# psu_ctrl_brd.net
KiCad netlist of a schematic drawn in EAGLE
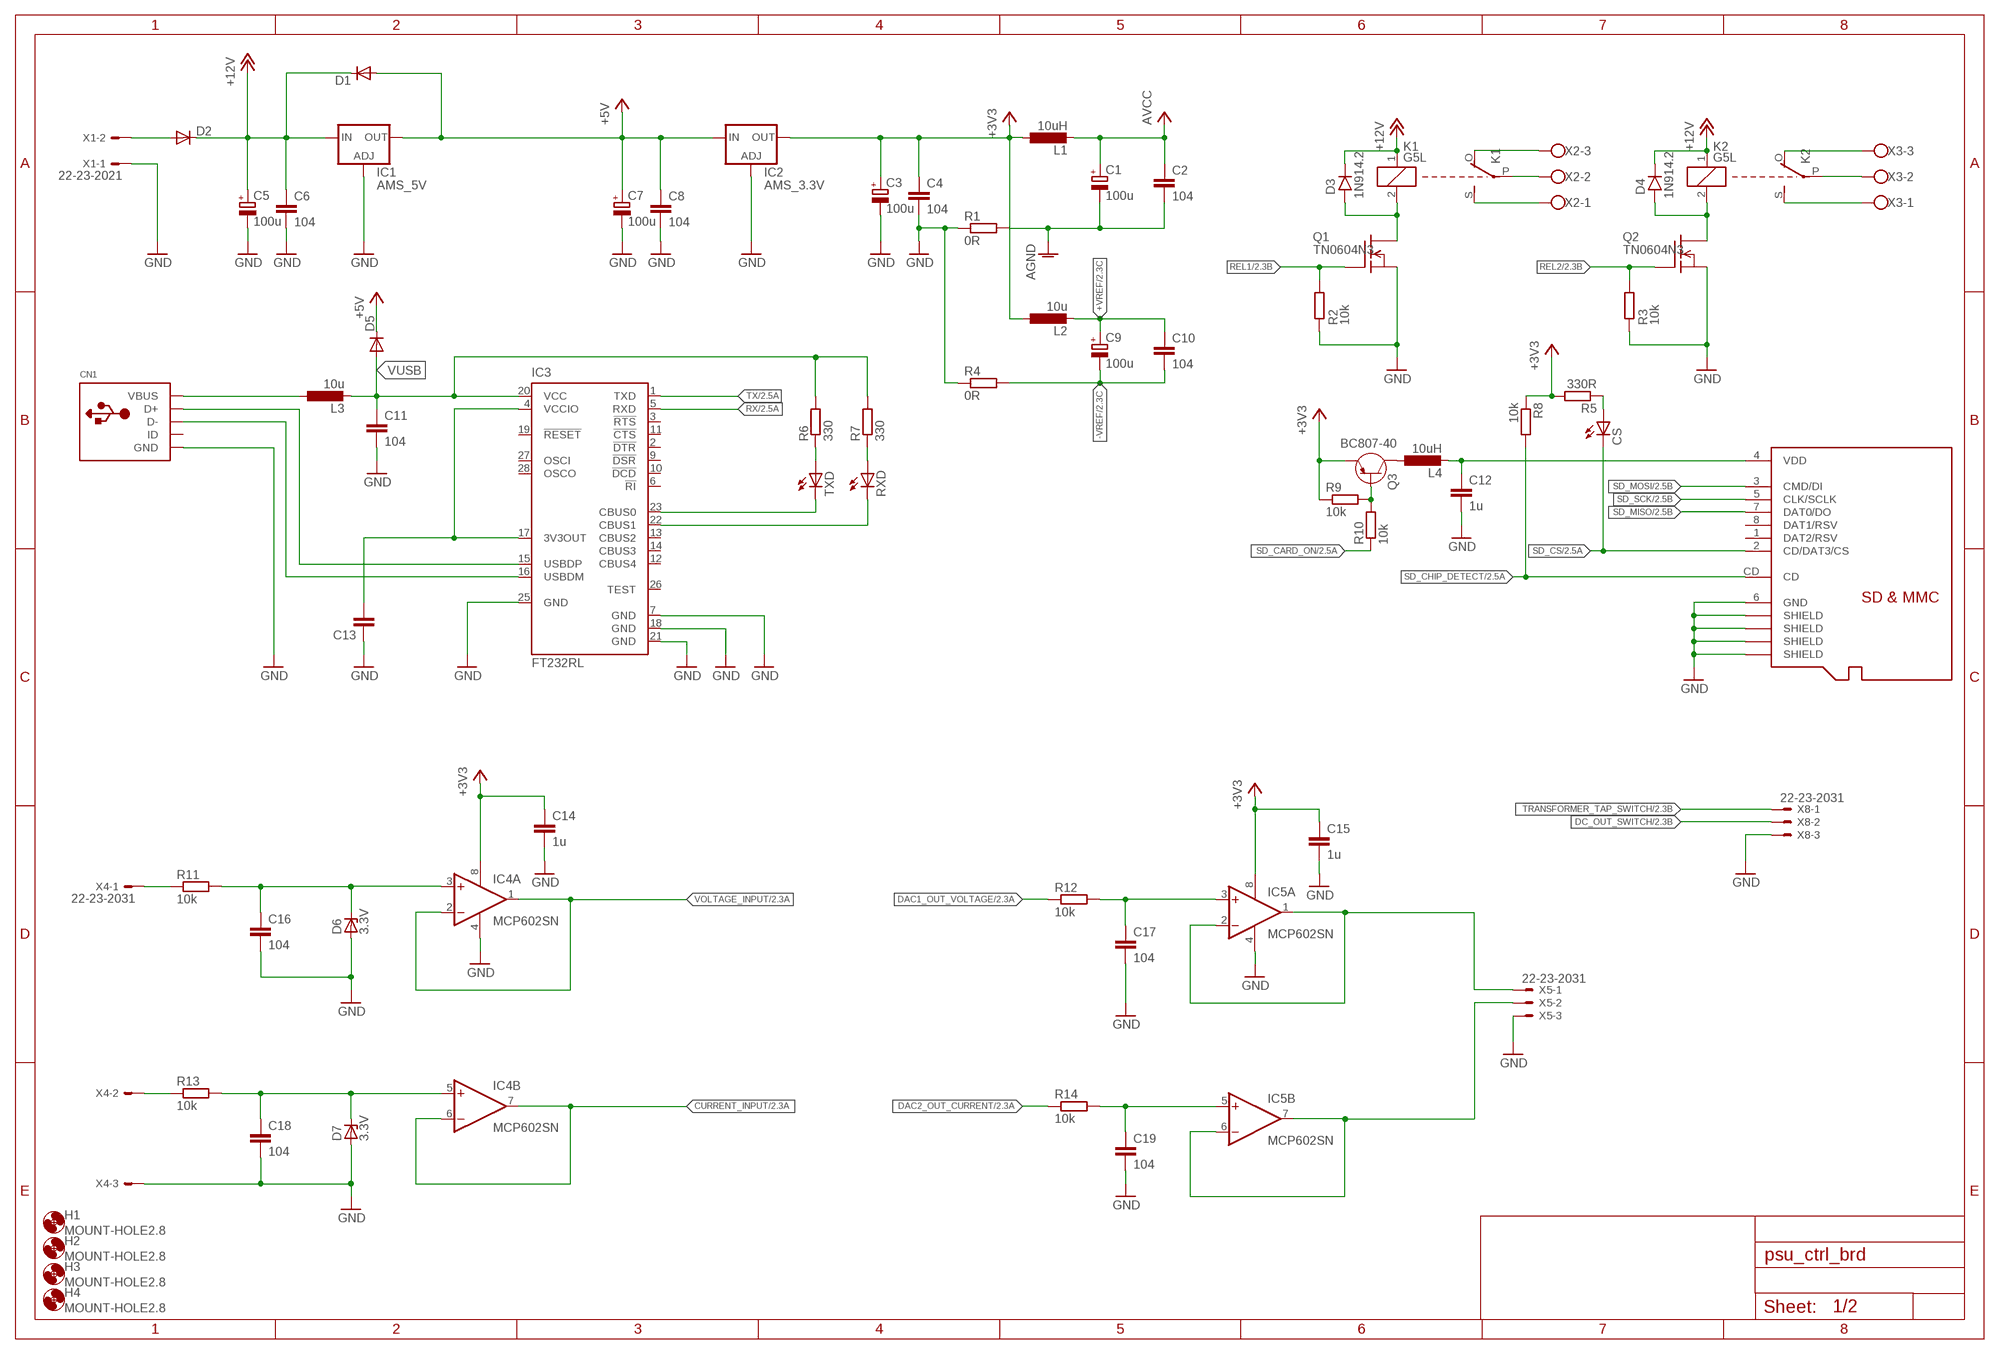
[diagram p0: schematic, sheet 1]
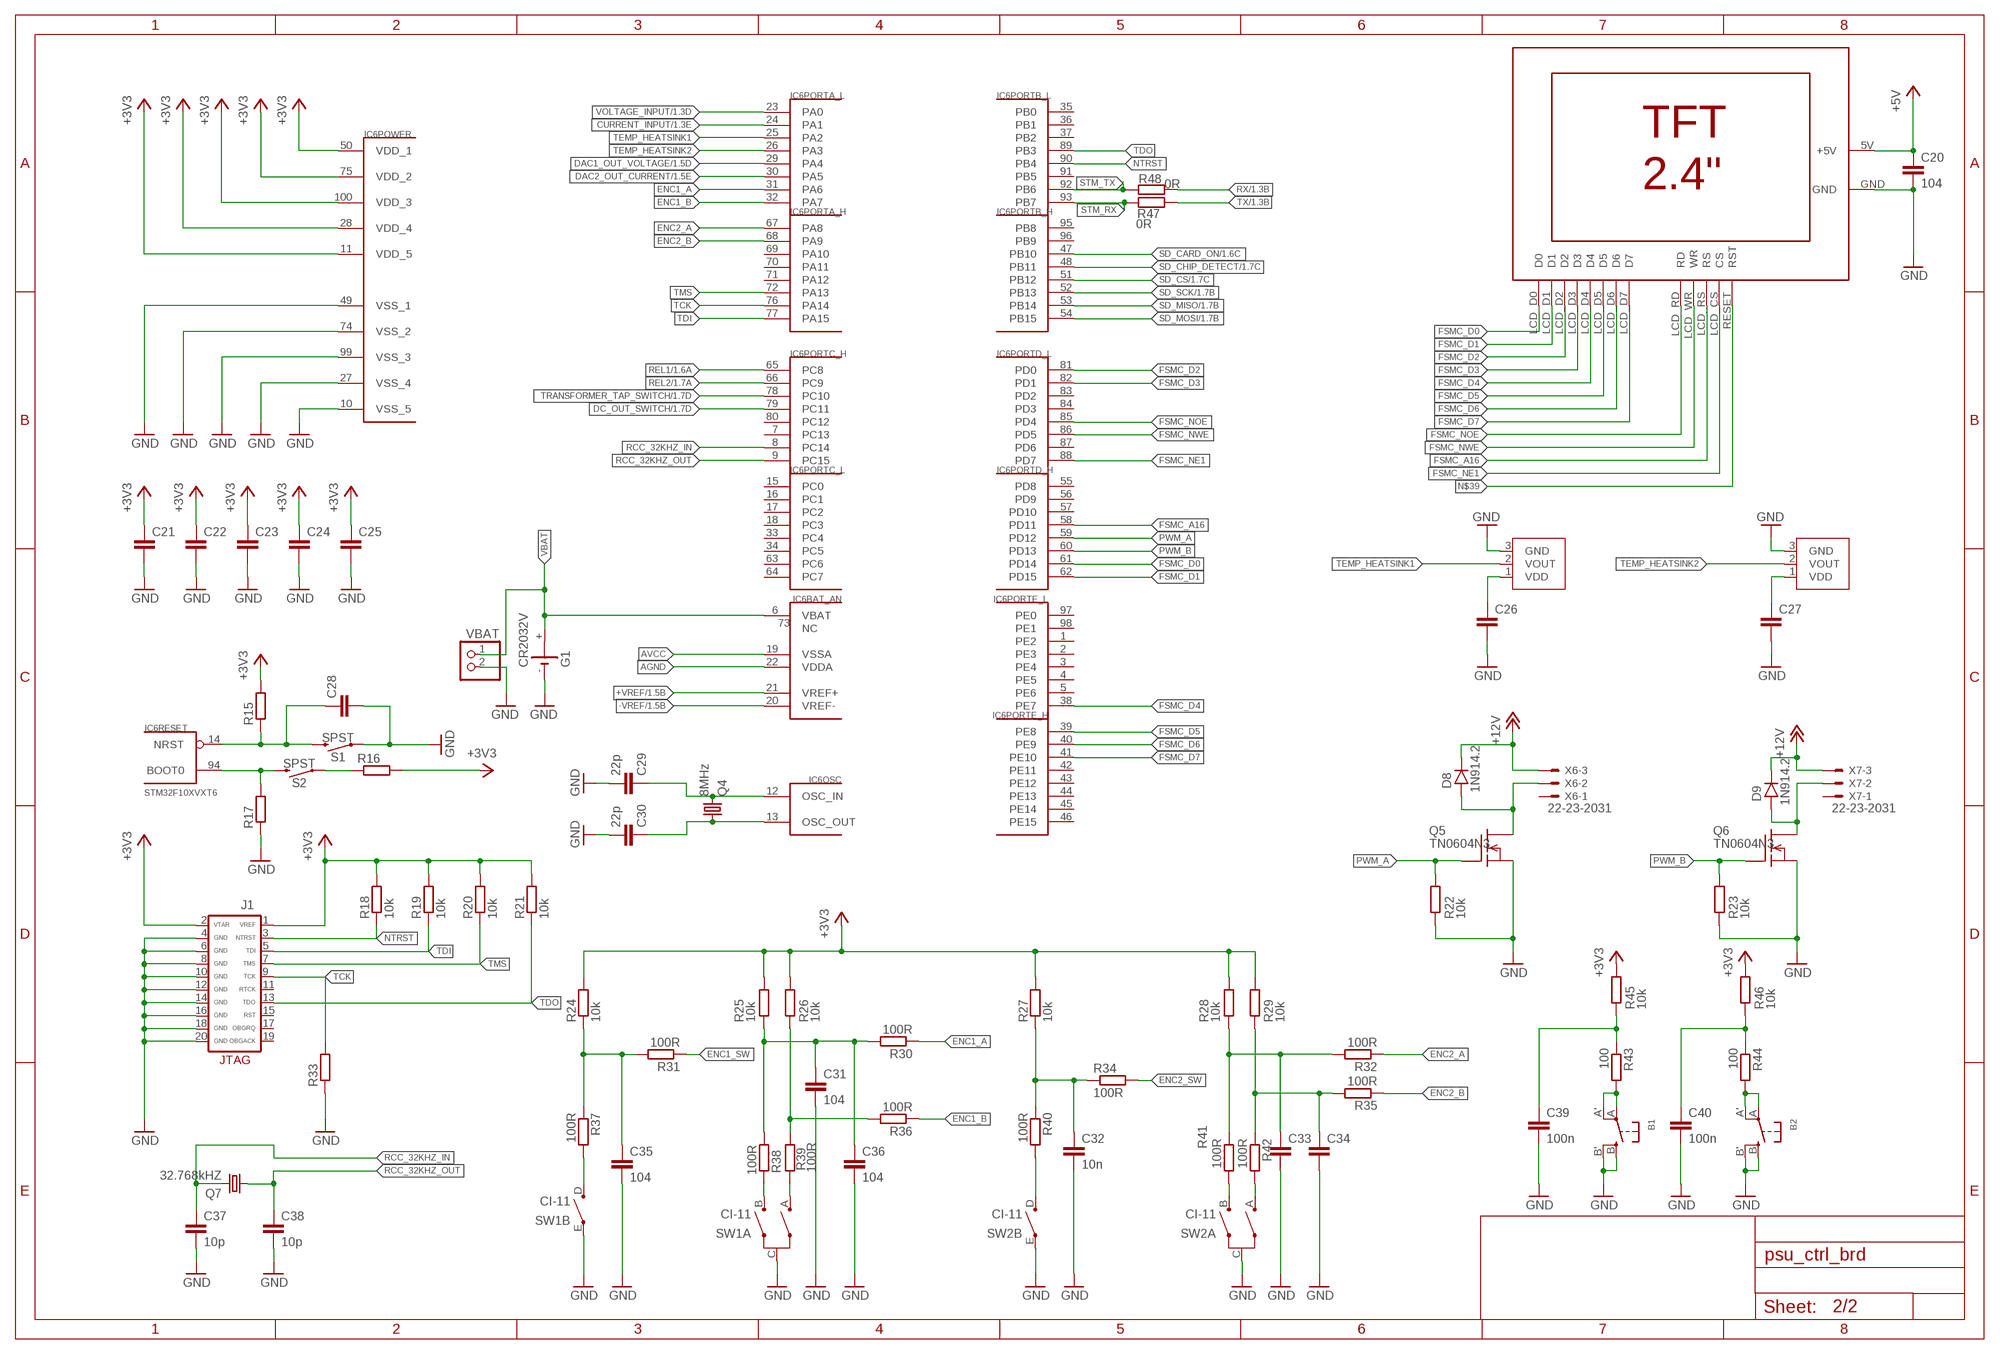
[diagram p1: schematic, sheet 2]

(export (version "E")
  (design (tool "Eeschema 10.0.6"))
  (components
    (comp (ref "B1")
      (value "SWITCH_TACT_SMT")
      (footprint "eagle-import:EVQ-Q2")
      (libsource (lib "eagle-import") (part "SWITCH_TACT_SMT"))
    )
    (comp (ref "B2")
      (value "SWITCH_TACT_SMT")
      (footprint "eagle-import:EVQ-Q2")
      (libsource (lib "eagle-import") (part "SWITCH_TACT_SMT"))
    )
    (comp (ref "C20")
      (value "104")
      (footprint "eagle-import:C0805")
      (libsource (lib "eagle-import") (part "C-EUC0805"))
    )
    (comp (ref "C21")
      (value "C-EUC0805")
      (footprint "eagle-import:C0805")
      (libsource (lib "eagle-import") (part "C-EUC0805"))
    )
    (comp (ref "C22")
      (value "C-EUC0805")
      (footprint "eagle-import:C0805")
      (libsource (lib "eagle-import") (part "C-EUC0805"))
    )
    (comp (ref "C23")
      (value "C-EUC0805")
      (footprint "eagle-import:C0805")
      (libsource (lib "eagle-import") (part "C-EUC0805"))
    )
    (comp (ref "C24")
      (value "C-EUC0805")
      (footprint "eagle-import:C0805")
      (libsource (lib "eagle-import") (part "C-EUC0805"))
    )
    (comp (ref "C25")
      (value "C-EUC0805")
      (footprint "eagle-import:C0805")
      (libsource (lib "eagle-import") (part "C-EUC0805"))
    )
    (comp (ref "C26")
      (value "C-EUC0805")
      (footprint "eagle-import:C0805")
      (libsource (lib "eagle-import") (part "C-EUC0805"))
    )
    (comp (ref "C27")
      (value "C-EUC0805")
      (footprint "eagle-import:C0805")
      (libsource (lib "eagle-import") (part "C-EUC0805"))
    )
    (comp (ref "C28")
      (value "C-EUC0805")
      (footprint "eagle-import:C0805")
      (libsource (lib "eagle-import") (part "C-EUC0805"))
    )
    (comp (ref "C29")
      (value "22p")
      (footprint "eagle-import:C0805")
      (libsource (lib "eagle-import") (part "C-EUC0805"))
    )
    (comp (ref "C30")
      (value "22p")
      (footprint "eagle-import:C0805")
      (libsource (lib "eagle-import") (part "C-EUC0805"))
    )
    (comp (ref "C31")
      (value "104")
      (footprint "eagle-import:C0805")
      (libsource (lib "eagle-import") (part "C-EUC0805"))
    )
    (comp (ref "C32")
      (value "10n")
      (footprint "eagle-import:C0805")
      (libsource (lib "eagle-import") (part "C-EUC0805"))
    )
    (comp (ref "C33")
      (value "C-EUC0805")
      (footprint "eagle-import:C0805")
      (libsource (lib "eagle-import") (part "C-EUC0805"))
    )
    (comp (ref "C34")
      (value "C-EUC0805")
      (footprint "eagle-import:C0805")
      (libsource (lib "eagle-import") (part "C-EUC0805"))
    )
    (comp (ref "C35")
      (value "104")
      (footprint "eagle-import:C0805")
      (libsource (lib "eagle-import") (part "C-EUC0805"))
    )
    (comp (ref "C36")
      (value "104")
      (footprint "eagle-import:C0805")
      (libsource (lib "eagle-import") (part "C-EUC0805"))
    )
    (comp (ref "C37")
      (value "10p")
      (footprint "eagle-import:C0805")
      (libsource (lib "eagle-import") (part "C-EUC0805"))
    )
    (comp (ref "C38")
      (value "10p")
      (footprint "eagle-import:C0805")
      (libsource (lib "eagle-import") (part "C-EUC0805"))
    )
    (comp (ref "C39")
      (value "100n")
      (footprint "eagle-import:C0805")
      (libsource (lib "eagle-import") (part "C-EUC0805"))
    )
    (comp (ref "C40")
      (value "100n")
      (footprint "eagle-import:C0805")
      (libsource (lib "eagle-import") (part "C-EUC0805"))
    )
    (comp (ref "D8")
      (value "1N914.2")
      (footprint "eagle-import:DO35-2")
      (libsource (lib "eagle-import") (part "1N914.2"))
    )
    (comp (ref "D9")
      (value "1N914.2")
      (footprint "eagle-import:DO35-2")
      (libsource (lib "eagle-import") (part "1N914.2"))
    )
    (comp (ref "G1")
      (value "CR2032V")
      (footprint "eagle-import:CR2032V")
      (libsource (lib "eagle-import") (part "CR2032V"))
    )
    (comp (ref "IC6")
      (value "STM32F10XVXT6")
      (footprint "eagle-import:TQFP100")
      (libsource (lib "eagle-import") (part "STM32F10XVXT6"))
    )
    (comp (ref "J1")
      (value "JTAG-ARM-PAK100/2500-20")
      (footprint "eagle-import:PAK100_2500-20")
      (libsource (lib "eagle-import") (part "JTAG-ARM-PAK100/2500-20"))
    )
    (comp (ref "MCP97X_1")
      (value "MCP970XTO")
      (footprint "eagle-import:TO92")
      (libsource (lib "eagle-import") (part "MCP970XTO"))
    )
    (comp (ref "MCP97X_2")
      (value "MCP970XTO")
      (footprint "eagle-import:TO92")
      (libsource (lib "eagle-import") (part "MCP970XTO"))
    )
    (comp (ref "Q4")
      (value "8MHz")
      (footprint "eagle-import:CSM-7X-DU")
      (libsource (lib "eagle-import") (part "CSM-7X-DU"))
    )
    (comp (ref "Q5")
      (value "TN0604N3")
      (footprint "eagle-import:TO-92")
      (libsource (lib "eagle-import") (part "TN0604N3"))
    )
    (comp (ref "Q6")
      (value "TN0604N3")
      (footprint "eagle-import:TO-92")
      (libsource (lib "eagle-import") (part "TN0604N3"))
    )
    (comp (ref "Q7")
      (value "32.768kHZ")
      (footprint "eagle-import:TC26V")
      (libsource (lib "eagle-import") (part "CRYSTALTC26V"))
    )
    (comp (ref "R15")
      (value "R-EU_R0805")
      (footprint "eagle-import:R0805")
      (libsource (lib "eagle-import") (part "R-EU_R0805"))
    )
    (comp (ref "R16")
      (value "R-EU_R0805")
      (footprint "eagle-import:R0805")
      (libsource (lib "eagle-import") (part "R-EU_R0805"))
    )
    (comp (ref "R17")
      (value "R-EU_R0805")
      (footprint "eagle-import:R0805")
      (libsource (lib "eagle-import") (part "R-EU_R0805"))
    )
    (comp (ref "R18")
      (value "10k")
      (footprint "eagle-import:R0805")
      (libsource (lib "eagle-import") (part "R-EU_R0805"))
    )
    (comp (ref "R19")
      (value "10k")
      (footprint "eagle-import:R0805")
      (libsource (lib "eagle-import") (part "R-EU_R0805"))
    )
    (comp (ref "R20")
      (value "10k")
      (footprint "eagle-import:R0805")
      (libsource (lib "eagle-import") (part "R-EU_R0805"))
    )
    (comp (ref "R21")
      (value "10k")
      (footprint "eagle-import:R0805")
      (libsource (lib "eagle-import") (part "R-EU_R0805"))
    )
    (comp (ref "R22")
      (value "10k")
      (footprint "eagle-import:R0805")
      (libsource (lib "eagle-import") (part "R-EU_R0805"))
    )
    (comp (ref "R23")
      (value "10k")
      (footprint "eagle-import:R0805")
      (libsource (lib "eagle-import") (part "R-EU_R0805"))
    )
    (comp (ref "R24")
      (value "10k")
      (footprint "eagle-import:R0805")
      (libsource (lib "eagle-import") (part "R-EU_R0805"))
    )
    (comp (ref "R25")
      (value "10k")
      (footprint "eagle-import:R0805")
      (libsource (lib "eagle-import") (part "R-EU_R0805"))
    )
    (comp (ref "R26")
      (value "10k")
      (footprint "eagle-import:R0805")
      (libsource (lib "eagle-import") (part "R-EU_R0805"))
    )
    (comp (ref "R27")
      (value "10k")
      (footprint "eagle-import:R0805")
      (libsource (lib "eagle-import") (part "R-EU_R0805"))
    )
    (comp (ref "R28")
      (value "10k")
      (footprint "eagle-import:R0805")
      (libsource (lib "eagle-import") (part "R-EU_R0805"))
    )
    (comp (ref "R29")
      (value "10k")
      (footprint "eagle-import:R0805")
      (libsource (lib "eagle-import") (part "R-EU_R0805"))
    )
    (comp (ref "R30")
      (value "100R")
      (footprint "eagle-import:R0805")
      (libsource (lib "eagle-import") (part "R-EU_R0805"))
    )
    (comp (ref "R31")
      (value "100R")
      (footprint "eagle-import:R0805")
      (libsource (lib "eagle-import") (part "R-EU_R0805"))
    )
    (comp (ref "R32")
      (value "100R")
      (footprint "eagle-import:R0805")
      (libsource (lib "eagle-import") (part "R-EU_R0805"))
    )
    (comp (ref "R33")
      (value "R-EU_R0805")
      (footprint "eagle-import:R0805")
      (libsource (lib "eagle-import") (part "R-EU_R0805"))
    )
    (comp (ref "R34")
      (value "100R")
      (footprint "eagle-import:R0805")
      (libsource (lib "eagle-import") (part "R-EU_R0805"))
    )
    (comp (ref "R35")
      (value "100R")
      (footprint "eagle-import:R0805")
      (libsource (lib "eagle-import") (part "R-EU_R0805"))
    )
    (comp (ref "R36")
      (value "100R")
      (footprint "eagle-import:R0805")
      (libsource (lib "eagle-import") (part "R-EU_R0805"))
    )
    (comp (ref "R37")
      (value "100R")
      (footprint "eagle-import:R0805")
      (libsource (lib "eagle-import") (part "R-EU_R0805"))
    )
    (comp (ref "R38")
      (value "100R")
      (footprint "eagle-import:R0805")
      (libsource (lib "eagle-import") (part "R-EU_R0805"))
    )
    (comp (ref "R39")
      (value "100R")
      (footprint "eagle-import:R0805")
      (libsource (lib "eagle-import") (part "R-EU_R0805"))
    )
    (comp (ref "R40")
      (value "100R")
      (footprint "eagle-import:R0805")
      (libsource (lib "eagle-import") (part "R-EU_R0805"))
    )
    (comp (ref "R41")
      (value "100R")
      (footprint "eagle-import:R0805")
      (libsource (lib "eagle-import") (part "R-EU_R0805"))
    )
    (comp (ref "R42")
      (value "100R")
      (footprint "eagle-import:R0805")
      (libsource (lib "eagle-import") (part "R-EU_R0805"))
    )
    (comp (ref "R43")
      (value "100")
      (footprint "eagle-import:R0805")
      (libsource (lib "eagle-import") (part "R-EU_R0805"))
    )
    (comp (ref "R44")
      (value "100")
      (footprint "eagle-import:R0805")
      (libsource (lib "eagle-import") (part "R-EU_R0805"))
    )
    (comp (ref "R45")
      (value "10k")
      (footprint "eagle-import:R0805")
      (libsource (lib "eagle-import") (part "R-EU_R0805"))
    )
    (comp (ref "R46")
      (value "10k")
      (footprint "eagle-import:R0805")
      (libsource (lib "eagle-import") (part "R-EU_R0805"))
    )
    (comp (ref "R47")
      (value "0R")
      (footprint "eagle-import:R0805")
      (libsource (lib "eagle-import") (part "R-EU_R0805"))
    )
    (comp (ref "R48")
      (value "0R")
      (footprint "eagle-import:R0805")
      (libsource (lib "eagle-import") (part "R-EU_R0805"))
    )
    (comp (ref "S1")
      (value "SPST")
      (footprint "eagle-import:TACTILE_SWITCH_SMD_6.0X3.5MM")
      (libsource (lib "eagle-import") (part "MOMENTARY-SWITCH-SPST-SMD-6.0X3.5MM"))
    )
    (comp (ref "S2")
      (value "SPST")
      (footprint "eagle-import:TACTILE_SWITCH_SMD_6.0X3.5MM")
      (libsource (lib "eagle-import") (part "MOMENTARY-SWITCH-SPST-SMD-6.0X3.5MM"))
    )
    (comp (ref "SW1")
      (value "CI-11")
      (footprint "eagle-import:CI-11")
      (libsource (lib "eagle-import") (part "CI-11"))
    )
    (comp (ref "SW2")
      (value "CI-11")
      (footprint "eagle-import:CI-11")
      (libsource (lib "eagle-import") (part "CI-11"))
    )
    (comp (ref "U$2")
      (value "TFT24")
      (footprint "eagle-import:A")
      (libsource (lib "eagle-import") (part "TFT24"))
    )
    (comp (ref "VBAT")
      (value "PINHD-1X2")
      (footprint "eagle-import:1X02")
      (libsource (lib "eagle-import") (part "PINHD-1X2"))
    )
    (comp (ref "X6")
      (value "22-23-2031")
      (footprint "eagle-import:22-23-2031")
      (fields (field (name "MF") "MOLEX"))
      (libsource (lib "eagle-import") (part "22-23-2031"))
    )
    (comp (ref "X7")
      (value "22-23-2031")
      (footprint "eagle-import:22-23-2031")
      (fields (field (name "MF") "MOLEX"))
      (libsource (lib "eagle-import") (part "22-23-2031"))
    )
    (comp (ref "C1")
      (value "100u")
      (footprint "eagle-import:153CLV-0505")
      (libsource (lib "eagle-import") (part "CPOL-EU153CLV-0505"))
    )
    (comp (ref "C2")
      (value "104")
      (footprint "eagle-import:C0805")
      (libsource (lib "eagle-import") (part "C-EUC0805"))
    )
    (comp (ref "C3")
      (value "100u")
      (footprint "eagle-import:153CLV-0505")
      (libsource (lib "eagle-import") (part "CPOL-EU153CLV-0505"))
    )
    (comp (ref "C4")
      (value "104")
      (footprint "eagle-import:C0805")
      (libsource (lib "eagle-import") (part "C-EUC0805"))
    )
    (comp (ref "C5")
      (value "100u")
      (footprint "eagle-import:153CLV-0505")
      (libsource (lib "eagle-import") (part "CPOL-EU153CLV-0505"))
    )
    (comp (ref "C6")
      (value "104")
      (footprint "eagle-import:C0805")
      (libsource (lib "eagle-import") (part "C-EUC0805"))
    )
    (comp (ref "C7")
      (value "100u")
      (footprint "eagle-import:153CLV-0505")
      (libsource (lib "eagle-import") (part "CPOL-EU153CLV-0505"))
    )
    (comp (ref "C8")
      (value "104")
      (footprint "eagle-import:C0805")
      (libsource (lib "eagle-import") (part "C-EUC0805"))
    )
    (comp (ref "C9")
      (value "100u")
      (footprint "eagle-import:153CLV-0505")
      (libsource (lib "eagle-import") (part "CPOL-EU153CLV-0505"))
    )
    (comp (ref "C10")
      (value "104")
      (footprint "eagle-import:C0805")
      (libsource (lib "eagle-import") (part "C-EUC0805"))
    )
    (comp (ref "C11")
      (value "104")
      (footprint "eagle-import:C0805")
      (libsource (lib "eagle-import") (part "C-EUC0805"))
    )
    (comp (ref "C12")
      (value "1u")
      (footprint "eagle-import:C0805")
      (libsource (lib "eagle-import") (part "C-EUC0805"))
    )
    (comp (ref "C13")
      (value "C-EUC0805")
      (footprint "eagle-import:C0805")
      (libsource (lib "eagle-import") (part "C-EUC0805"))
    )
    (comp (ref "C14")
      (value "1u")
      (footprint "eagle-import:C0805")
      (libsource (lib "eagle-import") (part "C-EUC0805"))
    )
    (comp (ref "C15")
      (value "1u")
      (footprint "eagle-import:C0805")
      (libsource (lib "eagle-import") (part "C-EUC0805"))
    )
    (comp (ref "C16")
      (value "104")
      (footprint "eagle-import:C0805")
      (libsource (lib "eagle-import") (part "C-EUC0805"))
    )
    (comp (ref "C17")
      (value "104")
      (footprint "eagle-import:C0805")
      (libsource (lib "eagle-import") (part "C-EUC0805"))
    )
    (comp (ref "C18")
      (value "104")
      (footprint "eagle-import:C0805")
      (libsource (lib "eagle-import") (part "C-EUC0805"))
    )
    (comp (ref "C19")
      (value "104")
      (footprint "eagle-import:C0805")
      (libsource (lib "eagle-import") (part "C-EUC0805"))
    )
    (comp (ref "CN1")
      (value "USBMINIB")
      (footprint "eagle-import:USB-MINIB")
      (libsource (lib "eagle-import") (part "USBMINIB"))
    )
    (comp (ref "CS")
      (value "LEDCHIPLED_1206")
      (footprint "eagle-import:CHIPLED_1206")
      (libsource (lib "eagle-import") (part "LEDCHIPLED_1206"))
    )
    (comp (ref "D1")
      (value "DIODE-DO-214AC")
      (footprint "eagle-import:DO-214AC")
      (libsource (lib "eagle-import") (part "DIODE-DO-214AC"))
    )
    (comp (ref "D2")
      (value "DIODE-DO-214AC")
      (footprint "eagle-import:DO-214AC")
      (libsource (lib "eagle-import") (part "DIODE-DO-214AC"))
    )
    (comp (ref "D3")
      (value "1N914.2")
      (footprint "eagle-import:DO35-2")
      (libsource (lib "eagle-import") (part "1N914.2"))
    )
    (comp (ref "D4")
      (value "1N914.2")
      (footprint "eagle-import:DO35-2")
      (libsource (lib "eagle-import") (part "1N914.2"))
    )
    (comp (ref "D5")
      (value "DIODE-DO-214AC")
      (footprint "eagle-import:DO-214AC")
      (libsource (lib "eagle-import") (part "DIODE-DO-214AC"))
    )
    (comp (ref "D6")
      (value "3.3V")
      (footprint "eagle-import:SOD81")
      (libsource (lib "eagle-import") (part "BZD23"))
    )
    (comp (ref "D7")
      (value "3.3V")
      (footprint "eagle-import:SOD81")
      (libsource (lib "eagle-import") (part "BZD23"))
    )
    (comp (ref "H1")
      (value "MOUNT-HOLE2.8")
      (footprint "eagle-import:2,8")
      (libsource (lib "eagle-import") (part "MOUNT-HOLE2.8"))
    )
    (comp (ref "H2")
      (value "MOUNT-HOLE2.8")
      (footprint "eagle-import:2,8")
      (libsource (lib "eagle-import") (part "MOUNT-HOLE2.8"))
    )
    (comp (ref "H3")
      (value "MOUNT-HOLE2.8")
      (footprint "eagle-import:2,8")
      (libsource (lib "eagle-import") (part "MOUNT-HOLE2.8"))
    )
    (comp (ref "H4")
      (value "MOUNT-HOLE2.8")
      (footprint "eagle-import:2,8")
      (libsource (lib "eagle-import") (part "MOUNT-HOLE2.8"))
    )
    (comp (ref "IC1")
      (value "AMS_5V")
      (footprint "eagle-import:SOT223")
      (libsource (lib "eagle-import") (part "LD117A?S50TR"))
    )
    (comp (ref "IC2")
      (value "AMS_3.3V")
      (footprint "eagle-import:SOT223")
      (libsource (lib "eagle-import") (part "LD117A?S50TR"))
    )
    (comp (ref "IC3")
      (value "FT232RL")
      (footprint "eagle-import:SSOP28")
      (libsource (lib "eagle-import") (part "FT232RL"))
    )
    (comp (ref "IC4")
      (value "MCP602SN")
      (footprint "eagle-import:SO08")
      (libsource (lib "eagle-import") (part "MCP602SN"))
    )
    (comp (ref "IC5")
      (value "MCP602SN")
      (footprint "eagle-import:SO08")
      (libsource (lib "eagle-import") (part "MCP602SN"))
    )
    (comp (ref "K1")
      (value "G5L")
      (footprint "eagle-import:G5LE")
      (libsource (lib "eagle-import") (part "G5L"))
    )
    (comp (ref "K2")
      (value "G5L")
      (footprint "eagle-import:G5LE")
      (libsource (lib "eagle-import") (part "G5L"))
    )
    (comp (ref "L1")
      (value "10uH")
      (footprint "eagle-import:0207_2V")
      (libsource (lib "eagle-import") (part "L-EU0207/2V"))
    )
    (comp (ref "L2")
      (value "10u")
      (footprint "eagle-import:0207_2V")
      (libsource (lib "eagle-import") (part "L-EU0207/2V"))
    )
    (comp (ref "L3")
      (value "10u")
      (footprint "eagle-import:0207_2V")
      (libsource (lib "eagle-import") (part "L-EU0207/2V"))
    )
    (comp (ref "L4")
      (value "10uH")
      (footprint "eagle-import:0207_2V")
      (libsource (lib "eagle-import") (part "L-EU0207/2V"))
    )
    (comp (ref "Q1")
      (value "TN0604N3")
      (footprint "eagle-import:TO-92")
      (libsource (lib "eagle-import") (part "TN0604N3"))
    )
    (comp (ref "Q2")
      (value "TN0604N3")
      (footprint "eagle-import:TO-92")
      (libsource (lib "eagle-import") (part "TN0604N3"))
    )
    (comp (ref "Q3")
      (value "BC807-40")
      (footprint "eagle-import:SOT23")
      (libsource (lib "eagle-import") (part "BC807-40"))
    )
    (comp (ref "R1")
      (value "0R")
      (footprint "eagle-import:M0805")
      (libsource (lib "eagle-import") (part "R-EU_M0805"))
    )
    (comp (ref "R2")
      (value "10k")
      (footprint "eagle-import:R0805")
      (libsource (lib "eagle-import") (part "R-EU_R0805"))
    )
    (comp (ref "R3")
      (value "10k")
      (footprint "eagle-import:R0805")
      (libsource (lib "eagle-import") (part "R-EU_R0805"))
    )
    (comp (ref "R4")
      (value "0R")
      (footprint "eagle-import:M0805")
      (libsource (lib "eagle-import") (part "R-EU_M0805"))
    )
    (comp (ref "R5")
      (value "330R")
      (footprint "eagle-import:M0805")
      (libsource (lib "eagle-import") (part "R-EU_M0805"))
    )
    (comp (ref "R6")
      (value "330")
      (footprint "eagle-import:M0805")
      (libsource (lib "eagle-import") (part "R-EU_M0805"))
    )
    (comp (ref "R7")
      (value "330")
      (footprint "eagle-import:M0805")
      (libsource (lib "eagle-import") (part "R-EU_M0805"))
    )
    (comp (ref "R8")
      (value "10k")
      (footprint "eagle-import:M0805")
      (libsource (lib "eagle-import") (part "R-EU_M0805"))
    )
    (comp (ref "R9")
      (value "10k")
      (footprint "eagle-import:M0805")
      (libsource (lib "eagle-import") (part "R-EU_M0805"))
    )
    (comp (ref "R10")
      (value "10k")
      (footprint "eagle-import:M0805")
      (libsource (lib "eagle-import") (part "R-EU_M0805"))
    )
    (comp (ref "R11")
      (value "10k")
      (footprint "eagle-import:M0805")
      (libsource (lib "eagle-import") (part "R-EU_M0805"))
    )
    (comp (ref "R12")
      (value "10k")
      (footprint "eagle-import:M0805")
      (libsource (lib "eagle-import") (part "R-EU_M0805"))
    )
    (comp (ref "R13")
      (value "10k")
      (footprint "eagle-import:M0805")
      (libsource (lib "eagle-import") (part "R-EU_M0805"))
    )
    (comp (ref "R14")
      (value "10k")
      (footprint "eagle-import:M0805")
      (libsource (lib "eagle-import") (part "R-EU_M0805"))
    )
    (comp (ref "RXD")
      (value "LEDCHIPLED_1206")
      (footprint "eagle-import:CHIPLED_1206")
      (libsource (lib "eagle-import") (part "LEDCHIPLED_1206"))
    )
    (comp (ref "TXD")
      (value "LEDCHIPLED_1206")
      (footprint "eagle-import:CHIPLED_1206")
      (libsource (lib "eagle-import") (part "LEDCHIPLED_1206"))
    )
    (comp (ref "U$1")
      (value "MICROSD")
      (footprint "eagle-import:C12075")
      (libsource (lib "eagle-import") (part "MICROSD"))
    )
    (comp (ref "X1")
      (value "22-23-2021")
      (footprint "eagle-import:22-23-2021")
      (fields (field (name "MF") "MOLEX"))
      (libsource (lib "eagle-import") (part "22-23-2021"))
    )
    (comp (ref "X2")
      (value "AK500/3")
      (footprint "eagle-import:AK500_3")
      (libsource (lib "eagle-import") (part "AK500/3"))
    )
    (comp (ref "X3")
      (value "AK500/3")
      (footprint "eagle-import:AK500_3")
      (libsource (lib "eagle-import") (part "AK500/3"))
    )
    (comp (ref "X4")
      (value "22-23-2031")
      (footprint "eagle-import:22-23-2031")
      (fields (field (name "MF") "MOLEX"))
      (libsource (lib "eagle-import") (part "22-23-2031"))
    )
    (comp (ref "X5")
      (value "22-23-2031")
      (footprint "eagle-import:22-23-2031")
      (fields (field (name "MF") "MOLEX"))
      (libsource (lib "eagle-import") (part "22-23-2031"))
    )
    (comp (ref "X8")
      (value "22-23-2031")
      (footprint "eagle-import:22-23-2031")
      (fields (field (name "MF") "MOLEX"))
      (libsource (lib "eagle-import") (part "22-23-2031"))
    )
  )
  (nets
    (net (code "1") (name "+3V3") (class "Default")
      (node (ref "C14") (pin "1") (pinfunction "1_1") (pintype "passive"))
      (node (ref "C15") (pin "1") (pinfunction "1_1") (pintype "passive"))
      (node (ref "C21") (pin "1") (pinfunction "1_1") (pintype "passive"))
      (node (ref "C22") (pin "1") (pinfunction "1_1") (pintype "passive"))
      (node (ref "C23") (pin "1") (pinfunction "1_1") (pintype "passive"))
      (node (ref "C24") (pin "1") (pinfunction "1_1") (pintype "passive"))
      (node (ref "C25") (pin "1") (pinfunction "1_1") (pintype "passive"))
      (node (ref "C3") (pin "+") (pinfunction "+_+") (pintype "passive"))
      (node (ref "C4") (pin "1") (pinfunction "1_1") (pintype "passive"))
      (node (ref "IC2") (pin "4") (pinfunction "OUT_4") (pintype "passive"))
      (node (ref "IC4") (pin "8") (pinfunction "V+_8") (pintype "power_in"))
      (node (ref "IC5") (pin "8") (pinfunction "V+_8") (pintype "power_in"))
      (node (ref "IC6") (pin "100") (pinfunction "VDD_3_100") (pintype "power_in"))
      (node (ref "IC6") (pin "11") (pinfunction "VDD_5_11") (pintype "power_in"))
      (node (ref "IC6") (pin "28") (pinfunction "VDD_4_28") (pintype "power_in"))
      (node (ref "IC6") (pin "50") (pinfunction "VDD_1_50") (pintype "power_in"))
      (node (ref "IC6") (pin "75") (pinfunction "VDD_2_75") (pintype "power_in"))
      (node (ref "J1") (pin "1") (pinfunction "VREF_1") (pintype "passive"))
      (node (ref "J1") (pin "2") (pinfunction "VTAR_2") (pintype "passive"))
      (node (ref "L1") (pin "1") (pinfunction "1_1") (pintype "passive"))
      (node (ref "L2") (pin "1") (pinfunction "1_1") (pintype "passive"))
      (node (ref "Q3") (pin "2") (pinfunction "E_2") (pintype "passive"))
      (node (ref "R15") (pin "2") (pinfunction "2_2") (pintype "passive"))
      (node (ref "R16") (pin "2") (pinfunction "2_2") (pintype "passive"))
      (node (ref "R18") (pin "2") (pinfunction "2_2") (pintype "passive"))
      (node (ref "R19") (pin "2") (pinfunction "2_2") (pintype "passive"))
      (node (ref "R20") (pin "2") (pinfunction "2_2") (pintype "passive"))
      (node (ref "R21") (pin "2") (pinfunction "2_2") (pintype "passive"))
      (node (ref "R24") (pin "2") (pinfunction "2_2") (pintype "passive"))
      (node (ref "R25") (pin "2") (pinfunction "2_2") (pintype "passive"))
      (node (ref "R26") (pin "2") (pinfunction "2_2") (pintype "passive"))
      (node (ref "R27") (pin "2") (pinfunction "2_2") (pintype "passive"))
      (node (ref "R28") (pin "2") (pinfunction "2_2") (pintype "passive"))
      (node (ref "R29") (pin "2") (pinfunction "2_2") (pintype "passive"))
      (node (ref "R45") (pin "2") (pinfunction "2_2") (pintype "passive"))
      (node (ref "R46") (pin "2") (pinfunction "2_2") (pintype "passive"))
      (node (ref "R5") (pin "2") (pinfunction "2_2") (pintype "passive"))
      (node (ref "R8") (pin "1") (pinfunction "1_1") (pintype "passive"))
      (node (ref "R9") (pin "1") (pinfunction "1_1") (pintype "passive"))
    )
    (net (code "2") (name "+5V") (class "Default")
      (node (ref "C20") (pin "1") (pinfunction "1_1") (pintype "passive"))
      (node (ref "C7") (pin "+") (pinfunction "+_+") (pintype "passive"))
      (node (ref "C8") (pin "1") (pinfunction "1_1") (pintype "passive"))
      (node (ref "D1") (pin "A") (pinfunction "A_A") (pintype "passive"))
      (node (ref "D5") (pin "C") (pinfunction "C_C") (pintype "passive"))
      (node (ref "IC1") (pin "4") (pinfunction "OUT_4") (pintype "passive"))
      (node (ref "IC2") (pin "3") (pinfunction "IN_3") (pintype "input"))
      (node (ref "U$2") (pin "5V") (pinfunction "+5V_5V") (pintype "bidirectional"))
    )
    (net (code "3") (name "+12V") (class "Default")
      (node (ref "C5") (pin "+") (pinfunction "+_+") (pintype "passive"))
      (node (ref "C6") (pin "1") (pinfunction "1_1") (pintype "passive"))
      (node (ref "D1") (pin "C") (pinfunction "C_C") (pintype "passive"))
      (node (ref "D2") (pin "C") (pinfunction "C_C") (pintype "passive"))
      (node (ref "D3") (pin "C") (pinfunction "C_C") (pintype "passive"))
      (node (ref "D4") (pin "C") (pinfunction "C_C") (pintype "passive"))
      (node (ref "D8") (pin "C") (pinfunction "C_C") (pintype "passive"))
      (node (ref "D9") (pin "C") (pinfunction "C_C") (pintype "passive"))
      (node (ref "IC1") (pin "3") (pinfunction "IN_3") (pintype "input"))
      (node (ref "K1") (pin "1") (pinfunction "1_1") (pintype "passive"))
      (node (ref "K2") (pin "1") (pinfunction "1_1") (pintype "passive"))
      (node (ref "X6") (pin "3") (pinfunction "S_3") (pintype "passive"))
      (node (ref "X7") (pin "3") (pinfunction "S_3") (pintype "passive"))
    )
    (net (code "4") (name "+VREF") (class "Default")
      (node (ref "C10") (pin "1") (pinfunction "1_1") (pintype "passive"))
      (node (ref "C9") (pin "+") (pinfunction "+_+") (pintype "passive"))
      (node (ref "IC6") (pin "21") (pinfunction "VREF+_21") (pintype "input"))
      (node (ref "L2") (pin "2") (pinfunction "2_2") (pintype "passive"))
    )
    (net (code "5") (name "-VREF") (class "Default")
      (node (ref "C10") (pin "2") (pinfunction "2_2") (pintype "passive"))
      (node (ref "C9") (pin "-") (pinfunction "-_-") (pintype "passive"))
      (node (ref "IC6") (pin "20") (pinfunction "VREF-_20") (pintype "input"))
      (node (ref "R4") (pin "2") (pinfunction "2_2") (pintype "passive"))
    )
    (net (code "6") (name "AGND") (class "Default")
      (node (ref "C1") (pin "-") (pinfunction "-_-") (pintype "passive"))
      (node (ref "C2") (pin "2") (pinfunction "2_2") (pintype "passive"))
      (node (ref "IC6") (pin "22") (pinfunction "VDDA_22") (pintype "power_in"))
      (node (ref "R1") (pin "2") (pinfunction "2_2") (pintype "passive"))
    )
    (net (code "7") (name "AVCC") (class "Default")
      (node (ref "C1") (pin "+") (pinfunction "+_+") (pintype "passive"))
      (node (ref "C2") (pin "1") (pinfunction "1_1") (pintype "passive"))
      (node (ref "IC6") (pin "19") (pinfunction "VSSA_19") (pintype "power_in"))
      (node (ref "L1") (pin "2") (pinfunction "2_2") (pintype "passive"))
    )
    (net (code "8") (name "CURRENT_INPUT") (class "Default")
      (node (ref "IC4") (pin "6") (pinfunction "-IN_6") (pintype "input"))
      (node (ref "IC4") (pin "7") (pinfunction "OUT_7") (pintype "output"))
      (node (ref "IC6") (pin "24") (pinfunction "PA1_24") (pintype "bidirectional"))
    )
    (net (code "9") (name "DAC1_OUT_VOLTAGE") (class "Default")
      (node (ref "IC6") (pin "29") (pinfunction "PA4_29") (pintype "bidirectional"))
      (node (ref "R12") (pin "1") (pinfunction "1_1") (pintype "passive"))
    )
    (net (code "10") (name "DAC2_OUT_CURRENT") (class "Default")
      (node (ref "IC6") (pin "30") (pinfunction "PA5_30") (pintype "bidirectional"))
      (node (ref "R14") (pin "1") (pinfunction "1_1") (pintype "passive"))
    )
    (net (code "11") (name "DC_OUT_SWITCH") (class "Default")
      (node (ref "IC6") (pin "79") (pinfunction "PC11_79") (pintype "bidirectional"))
      (node (ref "X8") (pin "2") (pinfunction "S_2") (pintype "passive"))
    )
    (net (code "12") (name "ENC1_A") (class "Default")
      (node (ref "C31") (pin "1") (pinfunction "1_1") (pintype "passive"))
      (node (ref "C36") (pin "1") (pinfunction "1_1") (pintype "passive"))
      (node (ref "IC6") (pin "31") (pinfunction "PA6_31") (pintype "bidirectional"))
      (node (ref "R25") (pin "1") (pinfunction "1_1") (pintype "passive"))
      (node (ref "R30") (pin "1") (pinfunction "1_1") (pintype "passive"))
      (node (ref "R30") (pin "2") (pinfunction "2_2") (pintype "passive"))
      (node (ref "R38") (pin "1") (pinfunction "1_1") (pintype "passive"))
    )
    (net (code "13") (name "ENC1_B") (class "Default")
      (node (ref "IC6") (pin "32") (pinfunction "PA7_32") (pintype "bidirectional"))
      (node (ref "R36") (pin "1") (pinfunction "1_1") (pintype "passive"))
    )
    (net (code "14") (name "ENC1_SW") (class "Default")
      (node (ref "R31") (pin "1") (pinfunction "1_1") (pintype "passive"))
    )
    (net (code "15") (name "ENC2_A") (class "Default")
      (node (ref "IC6") (pin "67") (pinfunction "PA8_67") (pintype "bidirectional"))
      (node (ref "R32") (pin "1") (pinfunction "1_1") (pintype "passive"))
    )
    (net (code "16") (name "ENC2_B") (class "Default")
      (node (ref "IC6") (pin "68") (pinfunction "PA9_68") (pintype "bidirectional"))
      (node (ref "R35") (pin "1") (pinfunction "1_1") (pintype "passive"))
    )
    (net (code "17") (name "ENC2_SW") (class "Default")
      (node (ref "R34") (pin "2") (pinfunction "2_2") (pintype "passive"))
    )
    (net (code "18") (name "FSMC_A16") (class "Default")
      (node (ref "IC6") (pin "58") (pinfunction "PD11_58") (pintype "bidirectional"))
      (node (ref "U$2") (pin "LCD_RS") (pinfunction "RS_LCD_RS") (pintype "bidirectional"))
    )
    (net (code "19") (name "FSMC_D0") (class "Default")
      (node (ref "IC6") (pin "61") (pinfunction "PD14_61") (pintype "bidirectional"))
      (node (ref "U$2") (pin "LCD_D0") (pinfunction "D0_LCD_D0") (pintype "bidirectional"))
    )
    (net (code "20") (name "FSMC_D1") (class "Default")
      (node (ref "IC6") (pin "62") (pinfunction "PD15_62") (pintype "bidirectional"))
      (node (ref "U$2") (pin "LCD_D1") (pinfunction "D1_LCD_D1") (pintype "bidirectional"))
    )
    (net (code "21") (name "FSMC_D2") (class "Default")
      (node (ref "IC6") (pin "81") (pinfunction "PD0_81") (pintype "bidirectional"))
      (node (ref "U$2") (pin "LCD_D2") (pinfunction "D2_LCD_D2") (pintype "bidirectional"))
    )
    (net (code "22") (name "FSMC_D3") (class "Default")
      (node (ref "IC6") (pin "82") (pinfunction "PD1_82") (pintype "bidirectional"))
      (node (ref "U$2") (pin "LCD_D3") (pinfunction "D3_LCD_D3") (pintype "bidirectional"))
    )
    (net (code "23") (name "FSMC_D4") (class "Default")
      (node (ref "IC6") (pin "38") (pinfunction "PE7_38") (pintype "bidirectional"))
      (node (ref "U$2") (pin "LCD_D4") (pinfunction "D4_LCD_D4") (pintype "bidirectional"))
    )
    (net (code "24") (name "FSMC_D5") (class "Default")
      (node (ref "IC6") (pin "39") (pinfunction "PE8_39") (pintype "bidirectional"))
      (node (ref "U$2") (pin "LCD_D5") (pinfunction "D5_LCD_D5") (pintype "bidirectional"))
    )
    (net (code "25") (name "FSMC_D6") (class "Default")
      (node (ref "IC6") (pin "40") (pinfunction "PE9_40") (pintype "bidirectional"))
      (node (ref "U$2") (pin "LCD_D6") (pinfunction "D6_LCD_D6") (pintype "bidirectional"))
    )
    (net (code "26") (name "FSMC_D7") (class "Default")
      (node (ref "IC6") (pin "41") (pinfunction "PE10_41") (pintype "bidirectional"))
      (node (ref "U$2") (pin "LCD_D7") (pinfunction "D7_LCD_D7") (pintype "bidirectional"))
    )
    (net (code "27") (name "FSMC_NE1") (class "Default")
      (node (ref "IC6") (pin "88") (pinfunction "PD7_88") (pintype "bidirectional"))
      (node (ref "U$2") (pin "LCD_CS") (pinfunction "CS_LCD_CS") (pintype "bidirectional"))
    )
    (net (code "28") (name "FSMC_NOE") (class "Default")
      (node (ref "IC6") (pin "85") (pinfunction "PD4_85") (pintype "bidirectional"))
      (node (ref "U$2") (pin "LCD_RD") (pinfunction "RD_LCD_RD") (pintype "bidirectional"))
    )
    (net (code "29") (name "FSMC_NWE") (class "Default")
      (node (ref "IC6") (pin "86") (pinfunction "PD5_86") (pintype "bidirectional"))
      (node (ref "U$2") (pin "LCD_WR") (pinfunction "WR_LCD_WR") (pintype "bidirectional"))
    )
    (net (code "30") (name "GND") (class "Default")
      (node (ref "B1") (pin "B") (pinfunction "S_B") (pintype "passive"))
      (node (ref "B1") (pin "B'") (pinfunction "S1_B'") (pintype "passive"))
      (node (ref "B2") (pin "B") (pinfunction "S_B") (pintype "passive"))
      (node (ref "B2") (pin "B'") (pinfunction "S1_B'") (pintype "passive"))
      (node (ref "C11") (pin "2") (pinfunction "2_2") (pintype "passive"))
      (node (ref "C12") (pin "2") (pinfunction "2_2") (pintype "passive"))
      (node (ref "C13") (pin "1") (pinfunction "1_1") (pintype "passive"))
      (node (ref "C14") (pin "2") (pinfunction "2_2") (pintype "passive"))
      (node (ref "C15") (pin "2") (pinfunction "2_2") (pintype "passive"))
      (node (ref "C16") (pin "2") (pinfunction "2_2") (pintype "passive"))
      (node (ref "C17") (pin "2") (pinfunction "2_2") (pintype "passive"))
      (node (ref "C18") (pin "2") (pinfunction "2_2") (pintype "passive"))
      (node (ref "C19") (pin "2") (pinfunction "2_2") (pintype "passive"))
      (node (ref "C20") (pin "2") (pinfunction "2_2") (pintype "passive"))
      (node (ref "C21") (pin "2") (pinfunction "2_2") (pintype "passive"))
      (node (ref "C22") (pin "2") (pinfunction "2_2") (pintype "passive"))
      (node (ref "C23") (pin "2") (pinfunction "2_2") (pintype "passive"))
      (node (ref "C24") (pin "2") (pinfunction "2_2") (pintype "passive"))
      (node (ref "C25") (pin "2") (pinfunction "2_2") (pintype "passive"))
      (node (ref "C26") (pin "2") (pinfunction "2_2") (pintype "passive"))
      (node (ref "C27") (pin "2") (pinfunction "2_2") (pintype "passive"))
      (node (ref "C28") (pin "2") (pinfunction "2_2") (pintype "passive"))
      (node (ref "C29") (pin "2") (pinfunction "2_2") (pintype "passive"))
      (node (ref "C3") (pin "-") (pinfunction "-_-") (pintype "passive"))
      (node (ref "C30") (pin "2") (pinfunction "2_2") (pintype "passive"))
      (node (ref "C31") (pin "2") (pinfunction "2_2") (pintype "passive"))
      (node (ref "C32") (pin "2") (pinfunction "2_2") (pintype "passive"))
      (node (ref "C33") (pin "2") (pinfunction "2_2") (pintype "passive"))
      (node (ref "C34") (pin "2") (pinfunction "2_2") (pintype "passive"))
      (node (ref "C35") (pin "2") (pinfunction "2_2") (pintype "passive"))
      (node (ref "C36") (pin "2") (pinfunction "2_2") (pintype "passive"))
      (node (ref "C37") (pin "2") (pinfunction "2_2") (pintype "passive"))
      (node (ref "C38") (pin "2") (pinfunction "2_2") (pintype "passive"))
      (node (ref "C39") (pin "2") (pinfunction "2_2") (pintype "passive"))
      (node (ref "C4") (pin "2") (pinfunction "2_2") (pintype "passive"))
      (node (ref "C40") (pin "2") (pinfunction "2_2") (pintype "passive"))
      (node (ref "C5") (pin "-") (pinfunction "-_-") (pintype "passive"))
      (node (ref "C6") (pin "2") (pinfunction "2_2") (pintype "passive"))
      (node (ref "C7") (pin "-") (pinfunction "-_-") (pintype "passive"))
      (node (ref "C8") (pin "2") (pinfunction "2_2") (pintype "passive"))
      (node (ref "CN1") (pin "GND") (pinfunction "GND_GND") (pintype "power_in"))
      (node (ref "D6") (pin "A") (pinfunction "A_A") (pintype "passive"))
      (node (ref "D7") (pin "A") (pinfunction "A_A") (pintype "passive"))
      (node (ref "G1") (pin "-") (pinfunction "-_-") (pintype "passive"))
      (node (ref "IC1") (pin "1") (pinfunction "ADJ_1") (pintype "input"))
      (node (ref "IC2") (pin "1") (pinfunction "ADJ_1") (pintype "input"))
      (node (ref "IC3") (pin "18") (pinfunction "GND_18") (pintype "power_in"))
      (node (ref "IC3") (pin "21") (pinfunction "GND_21") (pintype "power_in"))
      (node (ref "IC3") (pin "25") (pinfunction "GND_25") (pintype "power_in"))
      (node (ref "IC3") (pin "7") (pinfunction "GND_7") (pintype "power_in"))
      (node (ref "IC4") (pin "4") (pinfunction "V-_4") (pintype "power_in"))
      (node (ref "IC5") (pin "4") (pinfunction "V-_4") (pintype "power_in"))
      (node (ref "IC6") (pin "10") (pinfunction "VSS_5_10") (pintype "power_in"))
      (node (ref "IC6") (pin "27") (pinfunction "VSS_4_27") (pintype "power_in"))
      (node (ref "IC6") (pin "49") (pinfunction "VSS_1_49") (pintype "power_in"))
      (node (ref "IC6") (pin "74") (pinfunction "VSS_2_74") (pintype "power_in"))
      (node (ref "IC6") (pin "99") (pinfunction "VSS_3_99") (pintype "power_in"))
      (node (ref "J1") (pin "10") (pinfunction "GND_10") (pintype "passive"))
      (node (ref "J1") (pin "12") (pinfunction "GND_12") (pintype "passive"))
      (node (ref "J1") (pin "14") (pinfunction "GND_14") (pintype "passive"))
      (node (ref "J1") (pin "16") (pinfunction "GND_16") (pintype "passive"))
      (node (ref "J1") (pin "18") (pinfunction "GND_18") (pintype "passive"))
      (node (ref "J1") (pin "20") (pinfunction "GND_20") (pintype "passive"))
      (node (ref "J1") (pin "4") (pinfunction "GND_4") (pintype "passive"))
      (node (ref "J1") (pin "6") (pinfunction "GND_6") (pintype "passive"))
      (node (ref "J1") (pin "8") (pinfunction "GND_8") (pintype "passive"))
      (node (ref "MCP97X_1") (pin "3") (pinfunction "GND_3") (pintype "power_in"))
      (node (ref "MCP97X_2") (pin "3") (pinfunction "GND_3") (pintype "power_in"))
      (node (ref "Q1") (pin "1") (pinfunction "S_1") (pintype "passive"))
      (node (ref "Q2") (pin "1") (pinfunction "S_1") (pintype "passive"))
      (node (ref "Q5") (pin "1") (pinfunction "S_1") (pintype "passive"))
      (node (ref "Q6") (pin "1") (pinfunction "S_1") (pintype "passive"))
      (node (ref "R1") (pin "1") (pinfunction "1_1") (pintype "passive"))
      (node (ref "R17") (pin "1") (pinfunction "1_1") (pintype "passive"))
      (node (ref "R2") (pin "1") (pinfunction "1_1") (pintype "passive"))
      (node (ref "R22") (pin "1") (pinfunction "1_1") (pintype "passive"))
      (node (ref "R23") (pin "1") (pinfunction "1_1") (pintype "passive"))
      (node (ref "R3") (pin "1") (pinfunction "1_1") (pintype "passive"))
      (node (ref "R33") (pin "1") (pinfunction "1_1") (pintype "passive"))
      (node (ref "R4") (pin "1") (pinfunction "1_1") (pintype "passive"))
      (node (ref "S1") (pin "1") (pinfunction "1_1") (pintype "passive"))
      (node (ref "SW1") (pin "C") (pinfunction "C_C") (pintype "passive"))
      (node (ref "SW1") (pin "E") (pinfunction "E_E") (pintype "passive"))
      (node (ref "SW2") (pin "C") (pinfunction "C_C") (pintype "passive"))
      (node (ref "SW2") (pin "E") (pinfunction "E_E") (pintype "passive"))
      (node (ref "U$1") (pin "6") (pinfunction "GND_6") (pintype "power_in"))
      (node (ref "U$1") (pin "GND@1") (pinfunction "SHIELD_GND@1") (pintype "power_in"))
      (node (ref "U$1") (pin "GND@2") (pinfunction "SHIELD_GND@2") (pintype "power_in"))
      (node (ref "U$1") (pin "GND@3") (pinfunction "SHIELD_GND@3") (pintype "power_in"))
      (node (ref "U$1") (pin "GND@4") (pinfunction "SHIELD_GND@4") (pintype "power_in"))
      (node (ref "U$2") (pin "GND") (pinfunction "GND_GND") (pintype "bidirectional"))
      (node (ref "VBAT") (pin "2") (pinfunction "2_2") (pintype "passive"))
      (node (ref "X1") (pin "1") (pinfunction "S_1") (pintype "passive"))
      (node (ref "X4") (pin "3") (pinfunction "S_3") (pintype "passive"))
      (node (ref "X5") (pin "3") (pinfunction "S_3") (pintype "passive"))
      (node (ref "X8") (pin "3") (pinfunction "S_3") (pintype "passive"))
    )
    (net (code "31") (name "N$39") (class "Default")
      (node (ref "U$2") (pin "RESET") (pinfunction "RST_RESET") (pintype "bidirectional"))
    )
    (net (code "32") (name "NTRST") (class "Default")
      (node (ref "IC6") (pin "90") (pinfunction "PB4_90") (pintype "bidirectional"))
      (node (ref "J1") (pin "3") (pinfunction "NTRST_3") (pintype "passive"))
      (node (ref "R18") (pin "1") (pinfunction "1_1") (pintype "passive"))
    )
    (net (code "33") (name "Net-(B1-P)") (class "Default")
      (node (ref "B1") (pin "A") (pinfunction "P_A") (pintype "passive"))
      (node (ref "B1") (pin "A'") (pinfunction "P1_A'") (pintype "passive"))
      (node (ref "R43") (pin "2") (pinfunction "2_2") (pintype "passive"))
    )
    (net (code "34") (name "Net-(B2-P)") (class "Default")
      (node (ref "B2") (pin "A") (pinfunction "P_A") (pintype "passive"))
      (node (ref "B2") (pin "A'") (pinfunction "P1_A'") (pintype "passive"))
      (node (ref "R44") (pin "2") (pinfunction "2_2") (pintype "passive"))
    )
    (net (code "35") (name "Net-(C32-Pad1)") (class "Default")
      (node (ref "C32") (pin "1") (pinfunction "1_1") (pintype "passive"))
      (node (ref "R27") (pin "1") (pinfunction "1_1") (pintype "passive"))
      (node (ref "R34") (pin "1") (pinfunction "1_1") (pintype "passive"))
      (node (ref "R40") (pin "1") (pinfunction "1_1") (pintype "passive"))
    )
    (net (code "36") (name "Net-(C33-Pad1)") (class "Default")
      (node (ref "C33") (pin "1") (pinfunction "1_1") (pintype "passive"))
      (node (ref "R28") (pin "1") (pinfunction "1_1") (pintype "passive"))
      (node (ref "R32") (pin "2") (pinfunction "2_2") (pintype "passive"))
      (node (ref "R41") (pin "1") (pinfunction "1_1") (pintype "passive"))
    )
    (net (code "37") (name "Net-(C34-Pad1)") (class "Default")
      (node (ref "C34") (pin "1") (pinfunction "1_1") (pintype "passive"))
      (node (ref "R29") (pin "1") (pinfunction "1_1") (pintype "passive"))
      (node (ref "R35") (pin "2") (pinfunction "2_2") (pintype "passive"))
      (node (ref "R42") (pin "1") (pinfunction "1_1") (pintype "passive"))
    )
    (net (code "38") (name "Net-(C35-Pad1)") (class "Default")
      (node (ref "C35") (pin "1") (pinfunction "1_1") (pintype "passive"))
      (node (ref "R24") (pin "1") (pinfunction "1_1") (pintype "passive"))
      (node (ref "R31") (pin "2") (pinfunction "2_2") (pintype "passive"))
      (node (ref "R37") (pin "1") (pinfunction "1_1") (pintype "passive"))
    )
    (net (code "39") (name "Net-(C39-Pad1)") (class "Default")
      (node (ref "C39") (pin "1") (pinfunction "1_1") (pintype "passive"))
      (node (ref "R43") (pin "1") (pinfunction "1_1") (pintype "passive"))
      (node (ref "R45") (pin "1") (pinfunction "1_1") (pintype "passive"))
    )
    (net (code "40") (name "Net-(C40-Pad1)") (class "Default")
      (node (ref "C40") (pin "1") (pinfunction "1_1") (pintype "passive"))
      (node (ref "R44") (pin "1") (pinfunction "1_1") (pintype "passive"))
      (node (ref "R46") (pin "1") (pinfunction "1_1") (pintype "passive"))
    )
    (net (code "41") (name "Net-(CN1-PadVBUS)") (class "Default")
      (node (ref "CN1") (pin "VBUS") (pinfunction "VBUS_VBUS") (pintype "power_in"))
      (node (ref "L3") (pin "1") (pinfunction "1_1") (pintype "passive"))
    )
    (net (code "42") (name "Net-(CS-PadA)") (class "Default")
      (node (ref "CS") (pin "A") (pinfunction "A_A") (pintype "passive"))
      (node (ref "R5") (pin "1") (pinfunction "1_1") (pintype "passive"))
    )
    (net (code "43") (name "Net-(IC3-3V3OUT)") (class "Default")
      (node (ref "C13") (pin "2") (pinfunction "2_2") (pintype "passive"))
      (node (ref "IC3") (pin "17") (pinfunction "3V3OUT_17") (pintype "output"))
      (node (ref "IC3") (pin "4") (pinfunction "VCCIO_4") (pintype "power_in"))
    )
    (net (code "44") (name "Net-(IC3-CBUS0)") (class "Default")
      (node (ref "IC3") (pin "23") (pinfunction "CBUS0_23") (pintype "bidirectional"))
      (node (ref "TXD") (pin "C") (pinfunction "C_C") (pintype "passive"))
    )
    (net (code "45") (name "Net-(IC3-CBUS1)") (class "Default")
      (node (ref "IC3") (pin "22") (pinfunction "CBUS1_22") (pintype "bidirectional"))
      (node (ref "RXD") (pin "C") (pinfunction "C_C") (pintype "passive"))
    )
    (net (code "46") (name "Net-(IC3-USBDM)") (class "Default")
      (node (ref "CN1") (pin "D-") (pinfunction "D-_D-") (pintype "bidirectional"))
      (node (ref "IC3") (pin "16") (pinfunction "USBDM_16") (pintype "bidirectional"))
    )
    (net (code "47") (name "Net-(IC3-USBDP)") (class "Default")
      (node (ref "CN1") (pin "D+") (pinfunction "D+_D+") (pintype "bidirectional"))
      (node (ref "IC3") (pin "15") (pinfunction "USBDP_15") (pintype "bidirectional"))
    )
    (net (code "48") (name "Net-(IC4A-+IN)") (class "Default")
      (node (ref "C16") (pin "1") (pinfunction "1_1") (pintype "passive"))
      (node (ref "D6") (pin "C") (pinfunction "C_C") (pintype "passive"))
      (node (ref "IC4") (pin "3") (pinfunction "+IN_3") (pintype "input"))
      (node (ref "R11") (pin "2") (pinfunction "2_2") (pintype "passive"))
    )
    (net (code "49") (name "Net-(IC4B-+IN)") (class "Default")
      (node (ref "C18") (pin "1") (pinfunction "1_1") (pintype "passive"))
      (node (ref "D7") (pin "C") (pinfunction "C_C") (pintype "passive"))
      (node (ref "IC4") (pin "5") (pinfunction "+IN_5") (pintype "input"))
      (node (ref "R13") (pin "2") (pinfunction "2_2") (pintype "passive"))
    )
    (net (code "50") (name "Net-(IC5A-+IN)") (class "Default")
      (node (ref "C17") (pin "1") (pinfunction "1_1") (pintype "passive"))
      (node (ref "IC5") (pin "3") (pinfunction "+IN_3") (pintype "input"))
      (node (ref "R12") (pin "2") (pinfunction "2_2") (pintype "passive"))
    )
    (net (code "51") (name "Net-(IC5A--IN)") (class "Default")
      (node (ref "IC5") (pin "1") (pinfunction "OUT_1") (pintype "output"))
      (node (ref "IC5") (pin "2") (pinfunction "-IN_2") (pintype "input"))
      (node (ref "X5") (pin "1") (pinfunction "S_1") (pintype "passive"))
    )
    (net (code "52") (name "Net-(IC5B-+IN)") (class "Default")
      (node (ref "C19") (pin "1") (pinfunction "1_1") (pintype "passive"))
      (node (ref "IC5") (pin "5") (pinfunction "+IN_5") (pintype "input"))
      (node (ref "R14") (pin "2") (pinfunction "2_2") (pintype "passive"))
    )
    (net (code "53") (name "Net-(IC5B--IN)") (class "Default")
      (node (ref "IC5") (pin "6") (pinfunction "-IN_6") (pintype "input"))
      (node (ref "IC5") (pin "7") (pinfunction "OUT_7") (pintype "output"))
      (node (ref "X5") (pin "2") (pinfunction "S_2") (pintype "passive"))
    )
    (net (code "54") (name "Net-(IC6B-OSC_IN)") (class "Default")
      (node (ref "C29") (pin "1") (pinfunction "1_1") (pintype "passive"))
      (node (ref "IC6") (pin "12") (pinfunction "OSC_IN_12") (pintype "input"))
      (node (ref "Q4") (pin "2") (pinfunction "2_2") (pintype "passive"))
    )
    (net (code "55") (name "Net-(IC6B-OSC_OUT)") (class "Default")
      (node (ref "C30") (pin "1") (pinfunction "1_1") (pintype "passive"))
      (node (ref "IC6") (pin "13") (pinfunction "OSC_OUT_13") (pintype "output"))
      (node (ref "Q4") (pin "1") (pinfunction "1_1") (pintype "passive"))
    )
    (net (code "56") (name "Net-(IC6N-BOOT0)") (class "Default")
      (node (ref "IC6") (pin "94") (pinfunction "BOOT0_94") (pintype "input"))
      (node (ref "R17") (pin "2") (pinfunction "2_2") (pintype "passive"))
      (node (ref "S2") (pin "2") (pinfunction "2_2") (pintype "passive"))
    )
    (net (code "57") (name "Net-(IC6N-NRST)") (class "Default")
      (node (ref "C28") (pin "1") (pinfunction "1_1") (pintype "passive"))
      (node (ref "IC6") (pin "14") (pinfunction "NRST_14") (pintype "input"))
      (node (ref "R15") (pin "1") (pinfunction "1_1") (pintype "passive"))
      (node (ref "S1") (pin "2") (pinfunction "2_2") (pintype "passive"))
    )
    (net (code "58") (name "Net-(MCP97X_1-VDD)") (class "Default")
      (node (ref "C26") (pin "1") (pinfunction "1_1") (pintype "passive"))
      (node (ref "MCP97X_1") (pin "1") (pinfunction "VDD_1") (pintype "power_in"))
    )
    (net (code "59") (name "Net-(MCP97X_2-VDD)") (class "Default")
      (node (ref "C27") (pin "1") (pinfunction "1_1") (pintype "passive"))
      (node (ref "MCP97X_2") (pin "1") (pinfunction "VDD_1") (pintype "power_in"))
    )
    (net (code "60") (name "Net-(Q1-D)") (class "Default")
      (node (ref "D3") (pin "A") (pinfunction "A_A") (pintype "passive"))
      (node (ref "K1") (pin "2") (pinfunction "2_2") (pintype "passive"))
      (node (ref "Q1") (pin "3") (pinfunction "D_3") (pintype "passive"))
    )
    (net (code "61") (name "Net-(Q2-D)") (class "Default")
      (node (ref "D4") (pin "A") (pinfunction "A_A") (pintype "passive"))
      (node (ref "K2") (pin "2") (pinfunction "2_2") (pintype "passive"))
      (node (ref "Q2") (pin "3") (pinfunction "D_3") (pintype "passive"))
    )
    (net (code "62") (name "Net-(Q3-B)") (class "Default")
      (node (ref "Q3") (pin "1") (pinfunction "B_1") (pintype "passive"))
      (node (ref "R10") (pin "2") (pinfunction "2_2") (pintype "passive"))
      (node (ref "R9") (pin "2") (pinfunction "2_2") (pintype "passive"))
    )
    (net (code "63") (name "Net-(Q3-C)") (class "Default")
      (node (ref "L4") (pin "1") (pinfunction "1_1") (pintype "passive"))
      (node (ref "Q3") (pin "3") (pinfunction "C_3") (pintype "passive"))
    )
    (net (code "64") (name "Net-(Q5-D)") (class "Default")
      (node (ref "D8") (pin "A") (pinfunction "A_A") (pintype "passive"))
      (node (ref "Q5") (pin "3") (pinfunction "D_3") (pintype "passive"))
      (node (ref "X6") (pin "2") (pinfunction "S_2") (pintype "passive"))
    )
    (net (code "65") (name "Net-(Q6-D)") (class "Default")
      (node (ref "D9") (pin "A") (pinfunction "A_A") (pintype "passive"))
      (node (ref "Q6") (pin "3") (pinfunction "D_3") (pintype "passive"))
      (node (ref "X7") (pin "2") (pinfunction "S_2") (pintype "passive"))
    )
    (net (code "66") (name "Net-(R6-Pad1)") (class "Default")
      (node (ref "R6") (pin "1") (pinfunction "1_1") (pintype "passive"))
      (node (ref "TXD") (pin "A") (pinfunction "A_A") (pintype "passive"))
    )
    (net (code "67") (name "Net-(R7-Pad1)") (class "Default")
      (node (ref "R7") (pin "1") (pinfunction "1_1") (pintype "passive"))
      (node (ref "RXD") (pin "A") (pinfunction "A_A") (pintype "passive"))
    )
    (net (code "68") (name "Net-(R16-Pad1)") (class "Default")
      (node (ref "R16") (pin "1") (pinfunction "1_1") (pintype "passive"))
      (node (ref "S2") (pin "1") (pinfunction "1_1") (pintype "passive"))
    )
    (net (code "69") (name "Net-(R26-Pad1)") (class "Default")
      (node (ref "R26") (pin "1") (pinfunction "1_1") (pintype "passive"))
      (node (ref "R36") (pin "2") (pinfunction "2_2") (pintype "passive"))
      (node (ref "R39") (pin "1") (pinfunction "1_1") (pintype "passive"))
    )
    (net (code "70") (name "Net-(R37-Pad2)") (class "Default")
      (node (ref "R37") (pin "2") (pinfunction "2_2") (pintype "passive"))
      (node (ref "SW1") (pin "D") (pinfunction "D_D") (pintype "passive"))
    )
    (net (code "71") (name "Net-(R38-Pad2)") (class "Default")
      (node (ref "R38") (pin "2") (pinfunction "2_2") (pintype "passive"))
      (node (ref "SW1") (pin "B") (pinfunction "B_B") (pintype "passive"))
    )
    (net (code "72") (name "Net-(R39-Pad2)") (class "Default")
      (node (ref "R39") (pin "2") (pinfunction "2_2") (pintype "passive"))
      (node (ref "SW1") (pin "A") (pinfunction "A_A") (pintype "passive"))
    )
    (net (code "73") (name "Net-(R40-Pad2)") (class "Default")
      (node (ref "R40") (pin "2") (pinfunction "2_2") (pintype "passive"))
      (node (ref "SW2") (pin "D") (pinfunction "D_D") (pintype "passive"))
    )
    (net (code "74") (name "Net-(R41-Pad2)") (class "Default")
      (node (ref "R41") (pin "2") (pinfunction "2_2") (pintype "passive"))
      (node (ref "SW2") (pin "B") (pinfunction "B_B") (pintype "passive"))
    )
    (net (code "75") (name "Net-(R42-Pad2)") (class "Default")
      (node (ref "R42") (pin "2") (pinfunction "2_2") (pintype "passive"))
      (node (ref "SW2") (pin "A") (pinfunction "A_A") (pintype "passive"))
    )
    (net (code "76") (name "Net-(U$1-VDD)") (class "Default")
      (node (ref "C12") (pin "1") (pinfunction "1_1") (pintype "passive"))
      (node (ref "L4") (pin "2") (pinfunction "2_2") (pintype "passive"))
      (node (ref "U$1") (pin "4") (pinfunction "VDD_4") (pintype "power_in"))
    )
    (net (code "77") (name "Net-(X1B-S)") (class "Default")
      (node (ref "D2") (pin "A") (pinfunction "A_A") (pintype "passive"))
      (node (ref "X1") (pin "2") (pinfunction "S_2") (pintype "passive"))
    )
    (net (code "78") (name "Net-(X2A-KL)") (class "Default")
      (node (ref "K1") (pin "S") (pinfunction "S_S") (pintype "passive"))
      (node (ref "X2") (pin "1") (pinfunction "KL_1") (pintype "passive"))
    )
    (net (code "79") (name "Net-(X2B-KL)") (class "Default")
      (node (ref "K1") (pin "P") (pinfunction "P_P") (pintype "passive"))
      (node (ref "X2") (pin "2") (pinfunction "KL_2") (pintype "passive"))
    )
    (net (code "80") (name "Net-(X2C-KL)") (class "Default")
      (node (ref "K1") (pin "O") (pinfunction "O_O") (pintype "passive"))
      (node (ref "X2") (pin "3") (pinfunction "KL_3") (pintype "passive"))
    )
    (net (code "81") (name "Net-(X3A-KL)") (class "Default")
      (node (ref "K2") (pin "S") (pinfunction "S_S") (pintype "passive"))
      (node (ref "X3") (pin "1") (pinfunction "KL_1") (pintype "passive"))
    )
    (net (code "82") (name "Net-(X3B-KL)") (class "Default")
      (node (ref "K2") (pin "P") (pinfunction "P_P") (pintype "passive"))
      (node (ref "X3") (pin "2") (pinfunction "KL_2") (pintype "passive"))
    )
    (net (code "83") (name "Net-(X3C-KL)") (class "Default")
      (node (ref "K2") (pin "O") (pinfunction "O_O") (pintype "passive"))
      (node (ref "X3") (pin "3") (pinfunction "KL_3") (pintype "passive"))
    )
    (net (code "84") (name "Net-(X4A-S)") (class "Default")
      (node (ref "R11") (pin "1") (pinfunction "1_1") (pintype "passive"))
      (node (ref "X4") (pin "1") (pinfunction "S_1") (pintype "passive"))
    )
    (net (code "85") (name "Net-(X4B-S)") (class "Default")
      (node (ref "R13") (pin "1") (pinfunction "1_1") (pintype "passive"))
      (node (ref "X4") (pin "2") (pinfunction "S_2") (pintype "passive"))
    )
    (net (code "86") (name "PWM_A") (class "Default")
      (node (ref "IC6") (pin "59") (pinfunction "PD12_59") (pintype "bidirectional"))
      (node (ref "Q5") (pin "2") (pinfunction "G_2") (pintype "passive"))
      (node (ref "R22") (pin "2") (pinfunction "2_2") (pintype "passive"))
    )
    (net (code "87") (name "PWM_B") (class "Default")
      (node (ref "IC6") (pin "60") (pinfunction "PD13_60") (pintype "bidirectional"))
      (node (ref "Q6") (pin "2") (pinfunction "G_2") (pintype "passive"))
      (node (ref "R23") (pin "2") (pinfunction "2_2") (pintype "passive"))
    )
    (net (code "88") (name "RCC_32KHZ_IN") (class "Default")
      (node (ref "C37") (pin "1") (pinfunction "1_1") (pintype "passive"))
      (node (ref "IC6") (pin "8") (pinfunction "PC14_8") (pintype "bidirectional"))
      (node (ref "Q7") (pin "2") (pinfunction "2_2") (pintype "passive"))
    )
    (net (code "89") (name "RCC_32KHZ_OUT") (class "Default")
      (node (ref "C38") (pin "1") (pinfunction "1_1") (pintype "passive"))
      (node (ref "IC6") (pin "9") (pinfunction "PC15_9") (pintype "bidirectional"))
      (node (ref "Q7") (pin "1") (pinfunction "1_1") (pintype "passive"))
    )
    (net (code "90") (name "REL1") (class "Default")
      (node (ref "IC6") (pin "65") (pinfunction "PC8_65") (pintype "bidirectional"))
      (node (ref "Q1") (pin "2") (pinfunction "G_2") (pintype "passive"))
      (node (ref "R2") (pin "2") (pinfunction "2_2") (pintype "passive"))
    )
    (net (code "91") (name "REL2") (class "Default")
      (node (ref "IC6") (pin "66") (pinfunction "PC9_66") (pintype "bidirectional"))
      (node (ref "Q2") (pin "2") (pinfunction "G_2") (pintype "passive"))
      (node (ref "R3") (pin "2") (pinfunction "2_2") (pintype "passive"))
    )
    (net (code "92") (name "RX") (class "Default")
      (node (ref "IC3") (pin "5") (pinfunction "RXD_5") (pintype "input"))
      (node (ref "R48") (pin "2") (pinfunction "2_2") (pintype "passive"))
    )
    (net (code "93") (name "SD_CARD_ON") (class "Default")
      (node (ref "IC6") (pin "47") (pinfunction "PB10_47") (pintype "bidirectional"))
      (node (ref "R10") (pin "1") (pinfunction "1_1") (pintype "passive"))
    )
    (net (code "94") (name "SD_CHIP_DETECT") (class "Default")
      (node (ref "IC6") (pin "48") (pinfunction "PB11_48") (pintype "bidirectional"))
      (node (ref "R8") (pin "2") (pinfunction "2_2") (pintype "passive"))
      (node (ref "U$1") (pin "CD") (pinfunction "CD_CD") (pintype "bidirectional"))
    )
    (net (code "95") (name "SD_CS") (class "Default")
      (node (ref "CS") (pin "C") (pinfunction "C_C") (pintype "passive"))
      (node (ref "IC6") (pin "51") (pinfunction "PB12_51") (pintype "bidirectional"))
      (node (ref "U$1") (pin "2") (pinfunction "CD/DAT3/CS_2") (pintype "bidirectional"))
    )
    (net (code "96") (name "SD_MISO") (class "Default")
      (node (ref "IC6") (pin "53") (pinfunction "PB14_53") (pintype "bidirectional"))
      (node (ref "U$1") (pin "7") (pinfunction "DAT0/DO_7") (pintype "bidirectional"))
    )
    (net (code "97") (name "SD_MOSI") (class "Default")
      (node (ref "IC6") (pin "54") (pinfunction "PB15_54") (pintype "bidirectional"))
      (node (ref "U$1") (pin "3") (pinfunction "CMD/DI_3") (pintype "bidirectional"))
    )
    (net (code "98") (name "SD_SCK") (class "Default")
      (node (ref "IC6") (pin "52") (pinfunction "PB13_52") (pintype "bidirectional"))
      (node (ref "U$1") (pin "5") (pinfunction "CLK/SCLK_5") (pintype "bidirectional"))
    )
    (net (code "99") (name "STM_RX") (class "Default")
      (node (ref "IC6") (pin "93") (pinfunction "PB7_93") (pintype "bidirectional"))
      (node (ref "R47") (pin "1") (pinfunction "1_1") (pintype "passive"))
    )
    (net (code "100") (name "STM_TX") (class "Default")
      (node (ref "IC6") (pin "92") (pinfunction "PB6_92") (pintype "bidirectional"))
      (node (ref "R48") (pin "1") (pinfunction "1_1") (pintype "passive"))
    )
    (net (code "101") (name "TCK") (class "Default")
      (node (ref "IC6") (pin "76") (pinfunction "PA14_76") (pintype "bidirectional"))
      (node (ref "J1") (pin "9") (pinfunction "TCK_9") (pintype "passive"))
      (node (ref "R33") (pin "2") (pinfunction "2_2") (pintype "passive"))
    )
    (net (code "102") (name "TDI") (class "Default")
      (node (ref "IC6") (pin "77") (pinfunction "PA15_77") (pintype "bidirectional"))
      (node (ref "J1") (pin "5") (pinfunction "TDI_5") (pintype "passive"))
      (node (ref "R19") (pin "1") (pinfunction "1_1") (pintype "passive"))
    )
    (net (code "103") (name "TDO") (class "Default")
      (node (ref "IC6") (pin "89") (pinfunction "PB3_89") (pintype "bidirectional"))
      (node (ref "J1") (pin "13") (pinfunction "TDO_13") (pintype "passive"))
      (node (ref "R21") (pin "1") (pinfunction "1_1") (pintype "passive"))
    )
    (net (code "104") (name "TEMP_HEATSINK1") (class "Default")
      (node (ref "IC6") (pin "25") (pinfunction "PA2_25") (pintype "bidirectional"))
      (node (ref "MCP97X_1") (pin "2") (pinfunction "VOUT_2") (pintype "output"))
    )
    (net (code "105") (name "TEMP_HEATSINK2") (class "Default")
      (node (ref "IC6") (pin "26") (pinfunction "PA3_26") (pintype "bidirectional"))
      (node (ref "MCP97X_2") (pin "2") (pinfunction "VOUT_2") (pintype "output"))
    )
    (net (code "106") (name "TMS") (class "Default")
      (node (ref "IC6") (pin "72") (pinfunction "PA13_72") (pintype "bidirectional"))
      (node (ref "J1") (pin "7") (pinfunction "TMS_7") (pintype "passive"))
      (node (ref "R20") (pin "1") (pinfunction "1_1") (pintype "passive"))
    )
    (net (code "107") (name "TRANSFORMER_TAP_SWITCH") (class "Default")
      (node (ref "IC6") (pin "78") (pinfunction "PC10_78") (pintype "bidirectional"))
      (node (ref "X8") (pin "1") (pinfunction "S_1") (pintype "passive"))
    )
    (net (code "108") (name "TX") (class "Default")
      (node (ref "IC3") (pin "1") (pinfunction "TXD_1") (pintype "output"))
      (node (ref "R47") (pin "2") (pinfunction "2_2") (pintype "passive"))
    )
    (net (code "109") (name "VBAT") (class "Default")
      (node (ref "G1") (pin "+") (pinfunction "+_+") (pintype "passive"))
      (node (ref "IC6") (pin "6") (pinfunction "VBAT_6") (pintype "power_in"))
      (node (ref "VBAT") (pin "1") (pinfunction "1_1") (pintype "passive"))
    )
    (net (code "110") (name "VOLTAGE_INPUT") (class "Default")
      (node (ref "IC4") (pin "1") (pinfunction "OUT_1") (pintype "output"))
      (node (ref "IC4") (pin "2") (pinfunction "-IN_2") (pintype "input"))
      (node (ref "IC6") (pin "23") (pinfunction "PA0_23") (pintype "bidirectional"))
    )
    (net (code "111") (name "VUSB") (class "Default")
      (node (ref "C11") (pin "1") (pinfunction "1_1") (pintype "passive"))
      (node (ref "D5") (pin "A") (pinfunction "A_A") (pintype "passive"))
      (node (ref "IC3") (pin "20") (pinfunction "VCC_20") (pintype "power_in"))
      (node (ref "L3") (pin "2") (pinfunction "2_2") (pintype "passive"))
      (node (ref "R6") (pin "2") (pinfunction "2_2") (pintype "passive"))
      (node (ref "R7") (pin "2") (pinfunction "2_2") (pintype "passive"))
    )
    (net (code "112") (name "unconnected-(CN1-PadID)") (class "Default")
      (node (ref "CN1") (pin "ID") (pinfunction "ID_ID") (pintype "bidirectional"))
    )
    (net (code "113") (name "unconnected-(G1-+-Pad+@1)") (class "Default")
      (node (ref "G1") (pin "+@1") (pinfunction "+_+@1") (pintype "passive"))
    )
    (net (code "114") (name "unconnected-(IC3-CBUS2-Pad13)") (class "Default")
      (node (ref "IC3") (pin "13") (pinfunction "CBUS2_13") (pintype "bidirectional"))
    )
    (net (code "115") (name "unconnected-(IC3-CBUS3-Pad14)") (class "Default")
      (node (ref "IC3") (pin "14") (pinfunction "CBUS3_14") (pintype "bidirectional"))
    )
    (net (code "116") (name "unconnected-(IC3-CBUS4-Pad12)") (class "Default")
      (node (ref "IC3") (pin "12") (pinfunction "CBUS4_12") (pintype "bidirectional"))
    )
    (net (code "117") (name "unconnected-(IC3-OSCI-Pad27)") (class "Default")
      (node (ref "IC3") (pin "27") (pinfunction "OSCI_27") (pintype "input"))
    )
    (net (code "118") (name "unconnected-(IC3-OSCO-Pad28)") (class "Default")
      (node (ref "IC3") (pin "28") (pinfunction "OSCO_28") (pintype "output"))
    )
    (net (code "119") (name "unconnected-(IC3-TEST-Pad26)") (class "Default")
      (node (ref "IC3") (pin "26") (pinfunction "TEST_26") (pintype "input"))
    )
    (net (code "120") (name "unconnected-(IC3-~{CTS}-Pad11)") (class "Default")
      (node (ref "IC3") (pin "11") (pinfunction "~{CTS}_11") (pintype "input"))
    )
    (net (code "121") (name "unconnected-(IC3-~{DCD}-Pad10)") (class "Default")
      (node (ref "IC3") (pin "10") (pinfunction "~{DCD}_10") (pintype "input"))
    )
    (net (code "122") (name "unconnected-(IC3-~{DSR}-Pad9)") (class "Default")
      (node (ref "IC3") (pin "9") (pinfunction "~{DSR}_9") (pintype "input"))
    )
    (net (code "123") (name "unconnected-(IC3-~{DTR}-Pad2)") (class "Default")
      (node (ref "IC3") (pin "2") (pinfunction "~{DTR}_2") (pintype "output"))
    )
    (net (code "124") (name "unconnected-(IC3-~{RESET}-Pad19)") (class "Default")
      (node (ref "IC3") (pin "19") (pinfunction "~{RESET}_19") (pintype "input"))
    )
    (net (code "125") (name "unconnected-(IC3-~{RI}-Pad6)") (class "Default")
      (node (ref "IC3") (pin "6") (pinfunction "~{RI}_6") (pintype "input"))
    )
    (net (code "126") (name "unconnected-(IC3-~{RTS}-Pad3)") (class "Default")
      (node (ref "IC3") (pin "3") (pinfunction "~{RTS}_3") (pintype "output"))
    )
    (net (code "127") (name "unconnected-(IC6A-NC-Pad73)") (class "Default")
      (node (ref "IC6") (pin "73") (pinfunction "NC_73") (pintype "no_connect"))
    )
    (net (code "128") (name "unconnected-(IC6C-PA10-Pad69)") (class "Default")
      (node (ref "IC6") (pin "69") (pinfunction "PA10_69") (pintype "bidirectional"))
    )
    (net (code "129") (name "unconnected-(IC6C-PA11-Pad70)") (class "Default")
      (node (ref "IC6") (pin "70") (pinfunction "PA11_70") (pintype "bidirectional"))
    )
    (net (code "130") (name "unconnected-(IC6C-PA12-Pad71)") (class "Default")
      (node (ref "IC6") (pin "71") (pinfunction "PA12_71") (pintype "bidirectional"))
    )
    (net (code "131") (name "unconnected-(IC6E-PB8-Pad95)") (class "Default")
      (node (ref "IC6") (pin "95") (pinfunction "PB8_95") (pintype "bidirectional"))
    )
    (net (code "132") (name "unconnected-(IC6E-PB9-Pad96)") (class "Default")
      (node (ref "IC6") (pin "96") (pinfunction "PB9_96") (pintype "bidirectional"))
    )
    (net (code "133") (name "unconnected-(IC6F-PB0-Pad35)") (class "Default")
      (node (ref "IC6") (pin "35") (pinfunction "PB0_35") (pintype "bidirectional"))
    )
    (net (code "134") (name "unconnected-(IC6F-PB1-Pad36)") (class "Default")
      (node (ref "IC6") (pin "36") (pinfunction "PB1_36") (pintype "bidirectional"))
    )
    (net (code "135") (name "unconnected-(IC6F-PB2-Pad37)") (class "Default")
      (node (ref "IC6") (pin "37") (pinfunction "PB2_37") (pintype "bidirectional"))
    )
    (net (code "136") (name "unconnected-(IC6F-PB5-Pad91)") (class "Default")
      (node (ref "IC6") (pin "91") (pinfunction "PB5_91") (pintype "bidirectional"))
    )
    (net (code "137") (name "unconnected-(IC6G-PC12-Pad80)") (class "Default")
      (node (ref "IC6") (pin "80") (pinfunction "PC12_80") (pintype "bidirectional"))
    )
    (net (code "138") (name "unconnected-(IC6G-PC13-Pad7)") (class "Default")
      (node (ref "IC6") (pin "7") (pinfunction "PC13_7") (pintype "bidirectional"))
    )
    (net (code "139") (name "unconnected-(IC6H-PC0-Pad15)") (class "Default")
      (node (ref "IC6") (pin "15") (pinfunction "PC0_15") (pintype "bidirectional"))
    )
    (net (code "140") (name "unconnected-(IC6H-PC1-Pad16)") (class "Default")
      (node (ref "IC6") (pin "16") (pinfunction "PC1_16") (pintype "bidirectional"))
    )
    (net (code "141") (name "unconnected-(IC6H-PC2-Pad17)") (class "Default")
      (node (ref "IC6") (pin "17") (pinfunction "PC2_17") (pintype "bidirectional"))
    )
    (net (code "142") (name "unconnected-(IC6H-PC3-Pad18)") (class "Default")
      (node (ref "IC6") (pin "18") (pinfunction "PC3_18") (pintype "bidirectional"))
    )
    (net (code "143") (name "unconnected-(IC6H-PC4-Pad33)") (class "Default")
      (node (ref "IC6") (pin "33") (pinfunction "PC4_33") (pintype "bidirectional"))
    )
    (net (code "144") (name "unconnected-(IC6H-PC5-Pad34)") (class "Default")
      (node (ref "IC6") (pin "34") (pinfunction "PC5_34") (pintype "bidirectional"))
    )
    (net (code "145") (name "unconnected-(IC6H-PC6-Pad63)") (class "Default")
      (node (ref "IC6") (pin "63") (pinfunction "PC6_63") (pintype "bidirectional"))
    )
    (net (code "146") (name "unconnected-(IC6H-PC7-Pad64)") (class "Default")
      (node (ref "IC6") (pin "64") (pinfunction "PC7_64") (pintype "bidirectional"))
    )
    (net (code "147") (name "unconnected-(IC6I-PD8-Pad55)") (class "Default")
      (node (ref "IC6") (pin "55") (pinfunction "PD8_55") (pintype "bidirectional"))
    )
    (net (code "148") (name "unconnected-(IC6I-PD9-Pad56)") (class "Default")
      (node (ref "IC6") (pin "56") (pinfunction "PD9_56") (pintype "bidirectional"))
    )
    (net (code "149") (name "unconnected-(IC6I-PD10-Pad57)") (class "Default")
      (node (ref "IC6") (pin "57") (pinfunction "PD10_57") (pintype "bidirectional"))
    )
    (net (code "150") (name "unconnected-(IC6J-PD2-Pad83)") (class "Default")
      (node (ref "IC6") (pin "83") (pinfunction "PD2_83") (pintype "bidirectional"))
    )
    (net (code "151") (name "unconnected-(IC6J-PD3-Pad84)") (class "Default")
      (node (ref "IC6") (pin "84") (pinfunction "PD3_84") (pintype "bidirectional"))
    )
    (net (code "152") (name "unconnected-(IC6J-PD6-Pad87)") (class "Default")
      (node (ref "IC6") (pin "87") (pinfunction "PD6_87") (pintype "bidirectional"))
    )
    (net (code "153") (name "unconnected-(IC6K-PE11-Pad42)") (class "Default")
      (node (ref "IC6") (pin "42") (pinfunction "PE11_42") (pintype "bidirectional"))
    )
    (net (code "154") (name "unconnected-(IC6K-PE12-Pad43)") (class "Default")
      (node (ref "IC6") (pin "43") (pinfunction "PE12_43") (pintype "bidirectional"))
    )
    (net (code "155") (name "unconnected-(IC6K-PE13-Pad44)") (class "Default")
      (node (ref "IC6") (pin "44") (pinfunction "PE13_44") (pintype "bidirectional"))
    )
    (net (code "156") (name "unconnected-(IC6K-PE14-Pad45)") (class "Default")
      (node (ref "IC6") (pin "45") (pinfunction "PE14_45") (pintype "bidirectional"))
    )
    (net (code "157") (name "unconnected-(IC6K-PE15-Pad46)") (class "Default")
      (node (ref "IC6") (pin "46") (pinfunction "PE15_46") (pintype "bidirectional"))
    )
    (net (code "158") (name "unconnected-(IC6L-PE0-Pad97)") (class "Default")
      (node (ref "IC6") (pin "97") (pinfunction "PE0_97") (pintype "bidirectional"))
    )
    (net (code "159") (name "unconnected-(IC6L-PE1-Pad98)") (class "Default")
      (node (ref "IC6") (pin "98") (pinfunction "PE1_98") (pintype "bidirectional"))
    )
    (net (code "160") (name "unconnected-(IC6L-PE2-Pad1)") (class "Default")
      (node (ref "IC6") (pin "1") (pinfunction "PE2_1") (pintype "bidirectional"))
    )
    (net (code "161") (name "unconnected-(IC6L-PE3-Pad2)") (class "Default")
      (node (ref "IC6") (pin "2") (pinfunction "PE3_2") (pintype "bidirectional"))
    )
    (net (code "162") (name "unconnected-(IC6L-PE4-Pad3)") (class "Default")
      (node (ref "IC6") (pin "3") (pinfunction "PE4_3") (pintype "bidirectional"))
    )
    (net (code "163") (name "unconnected-(IC6L-PE5-Pad4)") (class "Default")
      (node (ref "IC6") (pin "4") (pinfunction "PE5_4") (pintype "bidirectional"))
    )
    (net (code "164") (name "unconnected-(IC6L-PE6-Pad5)") (class "Default")
      (node (ref "IC6") (pin "5") (pinfunction "PE6_5") (pintype "bidirectional"))
    )
    (net (code "165") (name "unconnected-(J1-OBGACK-Pad19)") (class "Default")
      (node (ref "J1") (pin "19") (pinfunction "OBGACK_19") (pintype "passive"))
    )
    (net (code "166") (name "unconnected-(J1-OBGRQ-Pad17)") (class "Default")
      (node (ref "J1") (pin "17") (pinfunction "OBGRQ_17") (pintype "passive"))
    )
    (net (code "167") (name "unconnected-(J1-RST-Pad15)") (class "Default")
      (node (ref "J1") (pin "15") (pinfunction "RST_15") (pintype "passive"))
    )
    (net (code "168") (name "unconnected-(J1-RTCK-Pad11)") (class "Default")
      (node (ref "J1") (pin "11") (pinfunction "RTCK_11") (pintype "passive"))
    )
    (net (code "169") (name "unconnected-(U$1-DAT1{slash}RSV-Pad8)") (class "Default")
      (node (ref "U$1") (pin "8") (pinfunction "DAT1/RSV_8") (pintype "bidirectional"))
    )
    (net (code "170") (name "unconnected-(U$1-DAT2{slash}RSV-Pad1)") (class "Default")
      (node (ref "U$1") (pin "1") (pinfunction "DAT2/RSV_1") (pintype "bidirectional"))
    )
    (net (code "171") (name "unconnected-(X6A-S-Pad1)") (class "Default")
      (node (ref "X6") (pin "1") (pinfunction "S_1") (pintype "passive"))
    )
    (net (code "172") (name "unconnected-(X7A-S-Pad1)") (class "Default")
      (node (ref "X7") (pin "1") (pinfunction "S_1") (pintype "passive"))
    )
  )
)
